# Calliope_mini_rev1_0.net
KiCad netlist of a schematic drawn in EAGLE
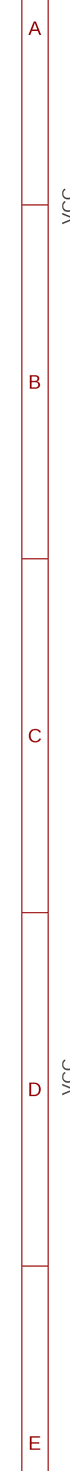
[diagram p0: schematic, sheet 1, part 1 of 2]
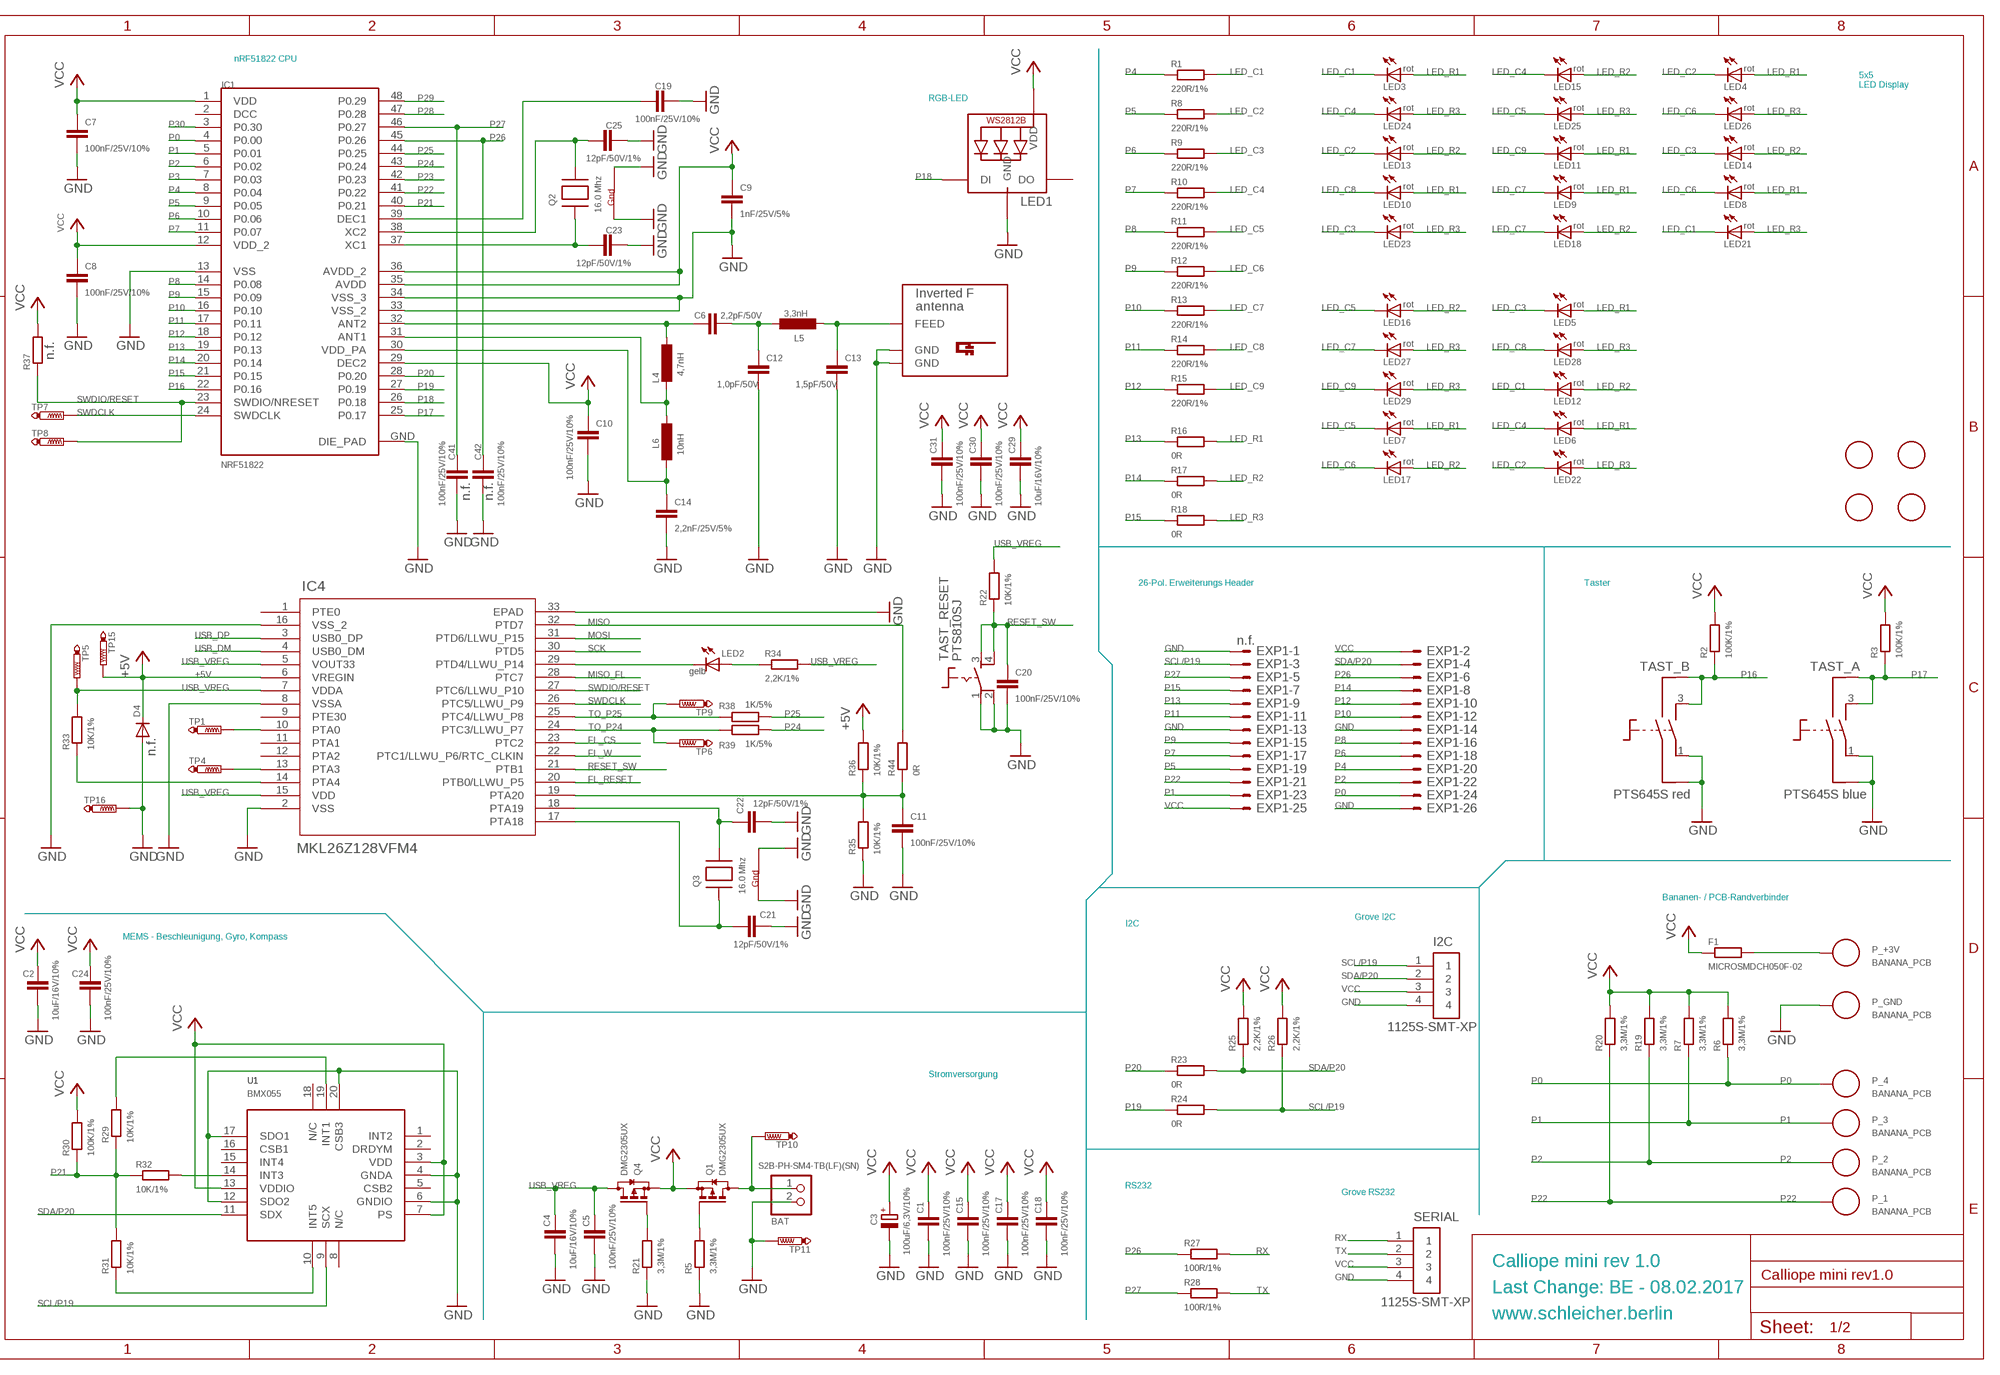
[diagram p1: schematic, sheet 1, part 2 of 2]
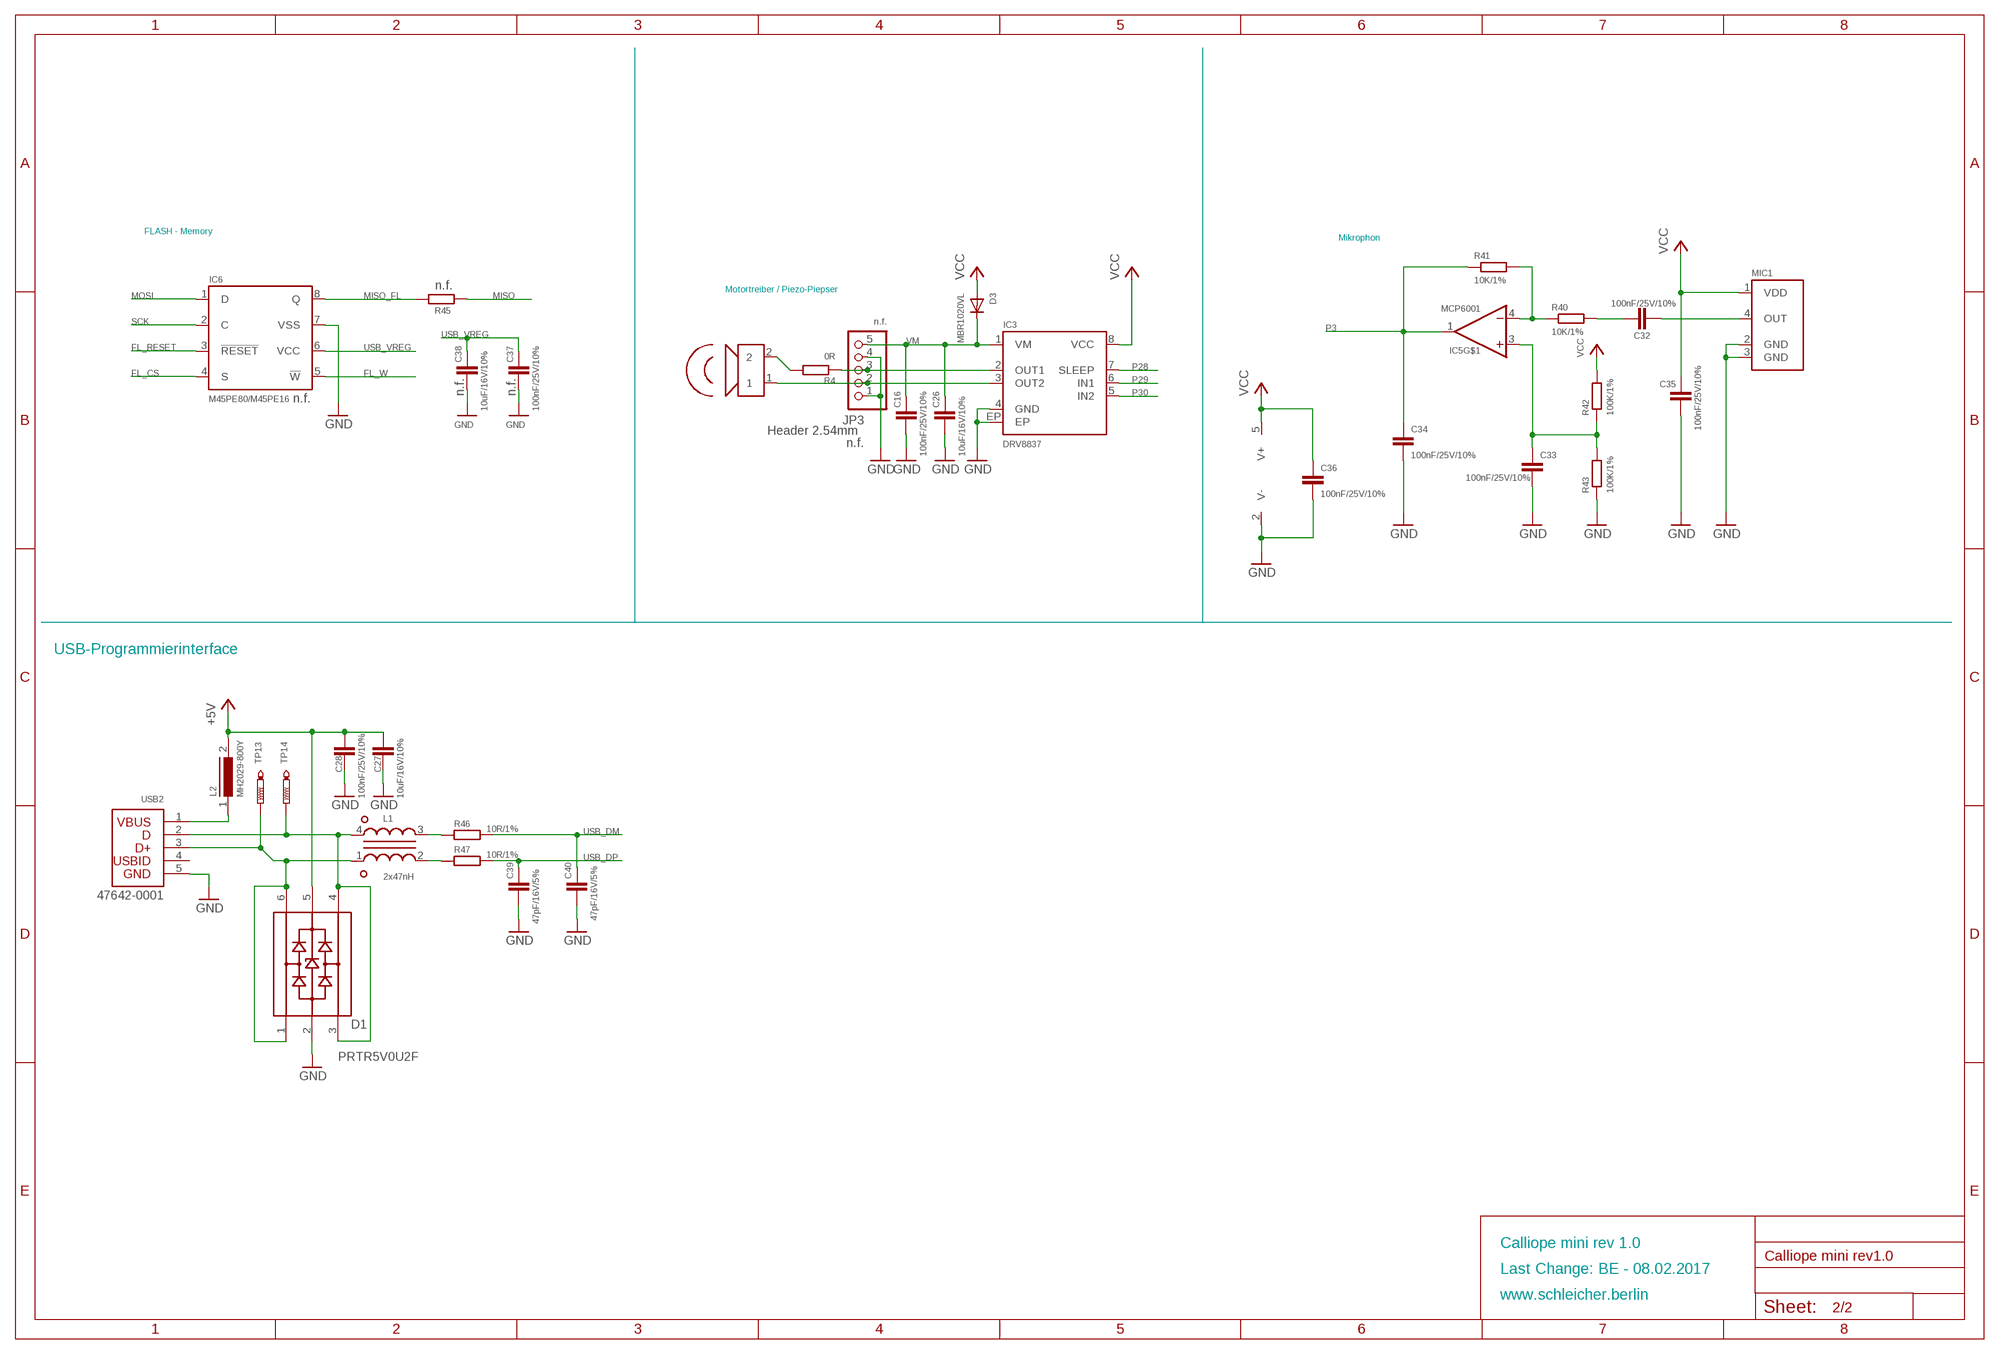
[diagram p2: schematic, sheet 2]

(export (version "E")
  (design (tool "Eeschema 10.0.6"))
  (components
    (comp (ref "C16")
      (value "100nF/25V/10%")
      (footprint "eagle-import:0402")
      (libsource (lib "eagle-import") (part "C-EU0402"))
    )
    (comp (ref "C26")
      (value "10uF/16V/10%")
      (footprint "eagle-import:0603")
      (libsource (lib "eagle-import") (part "C-EU0603"))
    )
    (comp (ref "C27")
      (value "10uF/16V/10%")
      (footprint "eagle-import:0603")
      (libsource (lib "eagle-import") (part "C-EU0603"))
    )
    (comp (ref "C28")
      (value "100nF/25V/10%")
      (footprint "eagle-import:0402")
      (libsource (lib "eagle-import") (part "C-EU0402"))
    )
    (comp (ref "C32")
      (value "100nF/25V/10%")
      (footprint "eagle-import:0402")
      (libsource (lib "eagle-import") (part "C-EU0402"))
    )
    (comp (ref "C33")
      (value "100nF/25V/10%")
      (footprint "eagle-import:0402")
      (libsource (lib "eagle-import") (part "C-EU0402"))
    )
    (comp (ref "C34")
      (value "100nF/25V/10%")
      (footprint "eagle-import:0402")
      (libsource (lib "eagle-import") (part "C-EU0402"))
    )
    (comp (ref "C35")
      (value "100nF/25V/10%")
      (footprint "eagle-import:0402")
      (libsource (lib "eagle-import") (part "C-EU0402"))
    )
    (comp (ref "C36")
      (value "100nF/25V/10%")
      (footprint "eagle-import:0402")
      (libsource (lib "eagle-import") (part "C-EU0402"))
    )
    (comp (ref "C37")
      (value "100nF/25V/10%")
      (footprint "eagle-import:0402")
      (fields (field (name "MOUNTING") "n.f."))
      (libsource (lib "eagle-import") (part "C-EU0402"))
    )
    (comp (ref "C38")
      (value "10uF/16V/10%")
      (footprint "eagle-import:0603")
      (fields (field (name "MOUNTING") "n.f."))
      (libsource (lib "eagle-import") (part "C-EU0603"))
    )
    (comp (ref "C39")
      (value "47pF/16V/5%")
      (footprint "eagle-import:0402")
      (libsource (lib "eagle-import") (part "C-EU0402"))
    )
    (comp (ref "C40")
      (value "47pF/16V/5%")
      (footprint "eagle-import:0402")
      (libsource (lib "eagle-import") (part "C-EU0402"))
    )
    (comp (ref "D1")
      (value "PRTR5V0U2F")
      (footprint "eagle-import:SOT886")
      (libsource (lib "eagle-import") (part "PRTR5V0U2F"))
    )
    (comp (ref "D3")
      (value "MBR1020VL")
      (footprint "eagle-import:SOD-123FL")
      (libsource (lib "eagle-import") (part "DIODE_SOD-123FL"))
    )
    (comp (ref "IC3")
      (value "DRV8837")
      (footprint "eagle-import:WSON8")
      (libsource (lib "eagle-import") (part "DRV8837"))
    )
    (comp (ref "IC5")
      (value "MCP6001")
      (footprint "eagle-import:SOT23-5")
      (libsource (lib "eagle-import") (part "OPAMP_SINGLESOT23-5"))
    )
    (comp (ref "IC6")
      (value "M45PE80/M45PE16")
      (footprint "eagle-import:VQFN8_6X5")
      (fields (field (name "MOUNTING") "n.f."))
      (libsource (lib "eagle-import") (part "M45PE"))
    )
    (comp (ref "JP3")
      (value "Header 2.54mm")
      (footprint "eagle-import:1X05")
      (fields (field (name "MOUNTING") "n.f."))
      (libsource (lib "eagle-import") (part "PINHD-1X5"))
    )
    (comp (ref "L1")
      (value "2x47nH")
      (footprint "eagle-import:USB_2.0_FILTER_0805")
      (libsource (lib "eagle-import") (part "0805USB-901MLC"))
    )
    (comp (ref "L2")
      (value "MH2029-800Y")
      (footprint "eagle-import:FERRIT_0805")
      (fields (field (name "TOLERANCE") "+-25%"))
      (libsource (lib "eagle-import") (part "MH2029-Y800"))
    )
    (comp (ref "MIC1")
      (value "SPU0410HR5H-PB")
      (footprint "eagle-import:SPU0410HR5H-PB")
      (libsource (lib "eagle-import") (part "SPU0410HR5H-PB"))
    )
    (comp (ref "R4")
      (value "0R")
      (footprint "eagle-import:0402")
      (libsource (lib "eagle-import") (part "R-EU_0402"))
    )
    (comp (ref "R40")
      (value "10K/1%")
      (footprint "eagle-import:0402")
      (libsource (lib "eagle-import") (part "R-EU_0402"))
    )
    (comp (ref "R41")
      (value "10K/1%")
      (footprint "eagle-import:0402")
      (libsource (lib "eagle-import") (part "R-EU_0402"))
    )
    (comp (ref "R42")
      (value "100K/1%")
      (footprint "eagle-import:0402")
      (libsource (lib "eagle-import") (part "R-EU_0402"))
    )
    (comp (ref "R43")
      (value "100K/1%")
      (footprint "eagle-import:0402")
      (libsource (lib "eagle-import") (part "R-EU_0402"))
    )
    (comp (ref "R45")
      (value "R-EU_0402")
      (footprint "eagle-import:0402")
      (fields (field (name "MOUNTING") "n.f."))
      (libsource (lib "eagle-import") (part "R-EU_0402"))
    )
    (comp (ref "R46")
      (value "10R/1%")
      (footprint "eagle-import:R0603")
      (libsource (lib "eagle-import") (part "resistor_R-EU_R0603"))
    )
    (comp (ref "R47")
      (value "10R/1%")
      (footprint "eagle-import:R0603")
      (libsource (lib "eagle-import") (part "resistor_R-EU_R0603"))
    )
    (comp (ref "SPK1")
      (value "PKMCS0909E4000-R1")
      (footprint "eagle-import:PKMCS")
      (libsource (lib "eagle-import") (part "PKMCS0909E4000-R1"))
    )
    (comp (ref "TP13")
      (value "PTR1B1,27")
      (footprint "eagle-import:B1,27")
      (libsource (lib "eagle-import") (part "PTR1B1,27"))
    )
    (comp (ref "TP14")
      (value "PTR1B1,27")
      (footprint "eagle-import:B1,27")
      (libsource (lib "eagle-import") (part "PTR1B1,27"))
    )
    (comp (ref "USB2")
      (value "47642-0001")
      (footprint "eagle-import:47642-0001")
      (libsource (lib "eagle-import") (part "47642-0001"))
    )
    (comp (ref "BAT")
      (value "S2B-PH-SM4-TB(LF)(SN)")
      (footprint "eagle-import:JST-PH-2-SMT-RA")
      (libsource (lib "eagle-import") (part "JST_2PIN-SMT-RA"))
    )
    (comp (ref "C1")
      (value "100nF/25V/10%")
      (footprint "eagle-import:0402")
      (libsource (lib "eagle-import") (part "C-EU0402"))
    )
    (comp (ref "C2")
      (value "10uF/16V/10%")
      (footprint "eagle-import:0603")
      (libsource (lib "eagle-import") (part "C-EU0603"))
    )
    (comp (ref "C3")
      (value "100uF/6,3V/10%")
      (footprint "eagle-import:D_7343-31R")
      (libsource (lib "eagle-import") (part "CPOL-EUD/7343-31R"))
    )
    (comp (ref "C4")
      (value "10uF/16V/10%")
      (footprint "eagle-import:0603")
      (libsource (lib "eagle-import") (part "C-EU0603"))
    )
    (comp (ref "C5")
      (value "100nF/25V/10%")
      (footprint "eagle-import:0402")
      (libsource (lib "eagle-import") (part "C-EU0402"))
    )
    (comp (ref "C6")
      (value "2,2pF/50V")
      (footprint "eagle-import:0402")
      (libsource (lib "eagle-import") (part "C-EU0402"))
    )
    (comp (ref "C7")
      (value "100nF/25V/10%")
      (footprint "eagle-import:0402")
      (libsource (lib "eagle-import") (part "C-EU0402"))
    )
    (comp (ref "C8")
      (value "100nF/25V/10%")
      (footprint "eagle-import:0402")
      (libsource (lib "eagle-import") (part "C-EU0402"))
    )
    (comp (ref "C9")
      (value "1nF/25V/5%")
      (footprint "eagle-import:0402")
      (libsource (lib "eagle-import") (part "C-EU0402"))
    )
    (comp (ref "C10")
      (value "100nF/25V/10%")
      (footprint "eagle-import:0402")
      (libsource (lib "eagle-import") (part "C-EU0402"))
    )
    (comp (ref "C11")
      (value "100nF/25V/10%")
      (footprint "eagle-import:0402")
      (libsource (lib "eagle-import") (part "C-EU0402"))
    )
    (comp (ref "C12")
      (value "1,0pF/50V")
      (footprint "eagle-import:0402")
      (libsource (lib "eagle-import") (part "C-EU0402"))
    )
    (comp (ref "C13")
      (value "1,5pF/50V")
      (footprint "eagle-import:0402")
      (libsource (lib "eagle-import") (part "C-EU0402"))
    )
    (comp (ref "C14")
      (value "2,2nF/25V/5%")
      (footprint "eagle-import:0402")
      (libsource (lib "eagle-import") (part "C-EU0402"))
    )
    (comp (ref "C15")
      (value "100nF/25V/10%")
      (footprint "eagle-import:0402")
      (libsource (lib "eagle-import") (part "C-EU0402"))
    )
    (comp (ref "C17")
      (value "100nF/25V/10%")
      (footprint "eagle-import:0402")
      (libsource (lib "eagle-import") (part "C-EU0402"))
    )
    (comp (ref "C18")
      (value "100nF/25V/10%")
      (footprint "eagle-import:0402")
      (libsource (lib "eagle-import") (part "C-EU0402"))
    )
    (comp (ref "C19")
      (value "100nF/25V/10%")
      (footprint "eagle-import:0402")
      (libsource (lib "eagle-import") (part "C-EU0402"))
    )
    (comp (ref "C20")
      (value "100nF/25V/10%")
      (footprint "eagle-import:0402")
      (libsource (lib "eagle-import") (part "C-EU0402"))
    )
    (comp (ref "C21")
      (value "12pF/50V/1%")
      (footprint "eagle-import:0402")
      (libsource (lib "eagle-import") (part "C-EU0402"))
    )
    (comp (ref "C22")
      (value "12pF/50V/1%")
      (footprint "eagle-import:0402")
      (libsource (lib "eagle-import") (part "C-EU0402"))
    )
    (comp (ref "C23")
      (value "12pF/50V/1%")
      (footprint "eagle-import:0402")
      (libsource (lib "eagle-import") (part "C-EU0402"))
    )
    (comp (ref "C24")
      (value "100nF/25V/10%")
      (footprint "eagle-import:0402")
      (libsource (lib "eagle-import") (part "C-EU0402"))
    )
    (comp (ref "C25")
      (value "12pF/50V/1%")
      (footprint "eagle-import:0402")
      (libsource (lib "eagle-import") (part "C-EU0402"))
    )
    (comp (ref "C29")
      (value "10uF/16V/10%")
      (footprint "eagle-import:0603")
      (libsource (lib "eagle-import") (part "C-EU0603"))
    )
    (comp (ref "C30")
      (value "100nF/25V/10%")
      (footprint "eagle-import:0402")
      (libsource (lib "eagle-import") (part "C-EU0402"))
    )
    (comp (ref "C31")
      (value "100nF/25V/10%")
      (footprint "eagle-import:0402")
      (libsource (lib "eagle-import") (part "C-EU0402"))
    )
    (comp (ref "C41")
      (value "100nF/25V/10%")
      (footprint "eagle-import:0402")
      (fields (field (name "MOUNTING") "n.f."))
      (libsource (lib "eagle-import") (part "C-EU0402"))
    )
    (comp (ref "C42")
      (value "100nF/25V/10%")
      (footprint "eagle-import:0402")
      (fields (field (name "MOUNTING") "n.f."))
      (libsource (lib "eagle-import") (part "C-EU0402"))
    )
    (comp (ref "D4")
      (value "DIODE-SOD323-R")
      (footprint "eagle-import:SOD323-R")
      (fields (field (name "MOUNTING") "n.f."))
      (libsource (lib "eagle-import") (part "DIODE-SOD323-R"))
    )
    (comp (ref "EXP1")
      (value "ML26E")
      (footprint "eagle-import:ML26")
      (fields (field (name "MOUNTING") "n.f."))
      (libsource (lib "eagle-import") (part "ML26?E"))
    )
    (comp (ref "F1")
      (value "MICROSMDCH050F-02")
      (footprint "eagle-import:R1210")
      (libsource (lib "eagle-import") (part "R-EU_R1210"))
    )
    (comp (ref "I2C")
      (value "1125S-SMT-XP")
      (footprint "eagle-import:1125S-SMT-XP")
      (libsource (lib "eagle-import") (part "1125-SMT-XPS"))
    )
    (comp (ref "IC1")
      (value "NRF51822")
      (footprint "eagle-import:QFN48")
      (libsource (lib "eagle-import") (part "NRF51822"))
    )
    (comp (ref "IC4")
      (value "MKL26Z128VFM4")
      (footprint "eagle-import:QFN_32_5X5X0P9")
      (libsource (lib "eagle-import") (part "MKL26Z"))
    )
    (comp (ref "L4")
      (value "4,7nH")
      (footprint "eagle-import:0402")
      (libsource (lib "eagle-import") (part "L-EU0402"))
    )
    (comp (ref "L5")
      (value "3,3nH")
      (footprint "eagle-import:0402")
      (libsource (lib "eagle-import") (part "L-EU0402"))
    )
    (comp (ref "L6")
      (value "10nH")
      (footprint "eagle-import:0402")
      (libsource (lib "eagle-import") (part "L-EU0402"))
    )
    (comp (ref "LED1")
      (value "SK6812MINI")
      (footprint "eagle-import:LED3535")
      (libsource (lib "eagle-import") (part "WS2812B3535"))
    )
    (comp (ref "LED2")
      (value "gelb")
      (footprint "eagle-import:CHIPLED_0603")
      (libsource (lib "eagle-import") (part "LEDCHIPLED_0603"))
    )
    (comp (ref "LED3")
      (value "rot")
      (footprint "eagle-import:CHIPLED_0603")
      (libsource (lib "eagle-import") (part "LEDCHIPLED_0603"))
    )
    (comp (ref "LED4")
      (value "rot")
      (footprint "eagle-import:CHIPLED_0603")
      (libsource (lib "eagle-import") (part "LEDCHIPLED_0603"))
    )
    (comp (ref "LED5")
      (value "rot")
      (footprint "eagle-import:CHIPLED_0603")
      (libsource (lib "eagle-import") (part "LEDCHIPLED_0603"))
    )
    (comp (ref "LED6")
      (value "rot")
      (footprint "eagle-import:CHIPLED_0603")
      (libsource (lib "eagle-import") (part "LEDCHIPLED_0603"))
    )
    (comp (ref "LED7")
      (value "rot")
      (footprint "eagle-import:CHIPLED_0603")
      (libsource (lib "eagle-import") (part "LEDCHIPLED_0603"))
    )
    (comp (ref "LED8")
      (value "rot")
      (footprint "eagle-import:CHIPLED_0603")
      (libsource (lib "eagle-import") (part "LEDCHIPLED_0603"))
    )
    (comp (ref "LED9")
      (value "rot")
      (footprint "eagle-import:CHIPLED_0603")
      (libsource (lib "eagle-import") (part "LEDCHIPLED_0603"))
    )
    (comp (ref "LED10")
      (value "rot")
      (footprint "eagle-import:CHIPLED_0603")
      (libsource (lib "eagle-import") (part "LEDCHIPLED_0603"))
    )
    (comp (ref "LED11")
      (value "rot")
      (footprint "eagle-import:CHIPLED_0603")
      (libsource (lib "eagle-import") (part "LEDCHIPLED_0603"))
    )
    (comp (ref "LED12")
      (value "rot")
      (footprint "eagle-import:CHIPLED_0603")
      (libsource (lib "eagle-import") (part "LEDCHIPLED_0603"))
    )
    (comp (ref "LED13")
      (value "rot")
      (footprint "eagle-import:CHIPLED_0603")
      (libsource (lib "eagle-import") (part "LEDCHIPLED_0603"))
    )
    (comp (ref "LED14")
      (value "rot")
      (footprint "eagle-import:CHIPLED_0603")
      (libsource (lib "eagle-import") (part "LEDCHIPLED_0603"))
    )
    (comp (ref "LED15")
      (value "rot")
      (footprint "eagle-import:CHIPLED_0603")
      (libsource (lib "eagle-import") (part "LEDCHIPLED_0603"))
    )
    (comp (ref "LED16")
      (value "rot")
      (footprint "eagle-import:CHIPLED_0603")
      (libsource (lib "eagle-import") (part "LEDCHIPLED_0603"))
    )
    (comp (ref "LED17")
      (value "rot")
      (footprint "eagle-import:CHIPLED_0603")
      (libsource (lib "eagle-import") (part "LEDCHIPLED_0603"))
    )
    (comp (ref "LED18")
      (value "rot")
      (footprint "eagle-import:CHIPLED_0603")
      (libsource (lib "eagle-import") (part "LEDCHIPLED_0603"))
    )
    (comp (ref "LED21")
      (value "rot")
      (footprint "eagle-import:CHIPLED_0603")
      (libsource (lib "eagle-import") (part "LEDCHIPLED_0603"))
    )
    (comp (ref "LED22")
      (value "rot")
      (footprint "eagle-import:CHIPLED_0603")
      (libsource (lib "eagle-import") (part "LEDCHIPLED_0603"))
    )
    (comp (ref "LED23")
      (value "rot")
      (footprint "eagle-import:CHIPLED_0603")
      (libsource (lib "eagle-import") (part "LEDCHIPLED_0603"))
    )
    (comp (ref "LED24")
      (value "rot")
      (footprint "eagle-import:CHIPLED_0603")
      (libsource (lib "eagle-import") (part "LEDCHIPLED_0603"))
    )
    (comp (ref "LED25")
      (value "rot")
      (footprint "eagle-import:CHIPLED_0603")
      (libsource (lib "eagle-import") (part "LEDCHIPLED_0603"))
    )
    (comp (ref "LED26")
      (value "rot")
      (footprint "eagle-import:CHIPLED_0603")
      (libsource (lib "eagle-import") (part "LEDCHIPLED_0603"))
    )
    (comp (ref "LED27")
      (value "rot")
      (footprint "eagle-import:CHIPLED_0603")
      (libsource (lib "eagle-import") (part "LEDCHIPLED_0603"))
    )
    (comp (ref "LED28")
      (value "rot")
      (footprint "eagle-import:CHIPLED_0603")
      (libsource (lib "eagle-import") (part "LEDCHIPLED_0603"))
    )
    (comp (ref "LED29")
      (value "rot")
      (footprint "eagle-import:CHIPLED_0603")
      (libsource (lib "eagle-import") (part "LEDCHIPLED_0603"))
    )
    (comp (ref "P_+3V")
      (value "BANANA_PCB")
      (footprint "eagle-import:BANANA_REC")
      (libsource (lib "eagle-import") (part "BANANA_PCB"))
    )
    (comp (ref "P_1")
      (value "BANANA_PCB")
      (footprint "eagle-import:BANANA_REC")
      (libsource (lib "eagle-import") (part "BANANA_PCB"))
    )
    (comp (ref "P_2")
      (value "BANANA_PCB")
      (footprint "eagle-import:BANANA_REC")
      (libsource (lib "eagle-import") (part "BANANA_PCB"))
    )
    (comp (ref "P_3")
      (value "BANANA_PCB")
      (footprint "eagle-import:BANANA_REC")
      (libsource (lib "eagle-import") (part "BANANA_PCB"))
    )
    (comp (ref "P_4")
      (value "BANANA_PCB")
      (footprint "eagle-import:BANANA_REC")
      (libsource (lib "eagle-import") (part "BANANA_PCB"))
    )
    (comp (ref "P_GND")
      (value "BANANA_PCB")
      (footprint "eagle-import:BANANA_REC")
      (libsource (lib "eagle-import") (part "BANANA_PCB"))
    )
    (comp (ref "Q1")
      (value "DMG2305UX")
      (footprint "eagle-import:SOT23")
      (libsource (lib "eagle-import") (part "BSS84"))
    )
    (comp (ref "Q2")
      (value "16.0 Mhz")
      (footprint "eagle-import:NX3225")
      (libsource (lib "eagle-import") (part "XTAL-4-3225"))
    )
    (comp (ref "Q3")
      (value "16.0 Mhz")
      (footprint "eagle-import:NX3225")
      (libsource (lib "eagle-import") (part "XTAL-4-3225"))
    )
    (comp (ref "Q4")
      (value "DMG2305UX")
      (footprint "eagle-import:SOT23")
      (libsource (lib "eagle-import") (part "BSS84"))
    )
    (comp (ref "R1")
      (value "220R/1%")
      (footprint "eagle-import:0402")
      (libsource (lib "eagle-import") (part "R-EU_0402"))
    )
    (comp (ref "R2")
      (value "100K/1%")
      (footprint "eagle-import:0402")
      (libsource (lib "eagle-import") (part "R-EU_0402"))
    )
    (comp (ref "R3")
      (value "100K/1%")
      (footprint "eagle-import:0402")
      (libsource (lib "eagle-import") (part "R-EU_0402"))
    )
    (comp (ref "R5")
      (value "3,3M/1%")
      (footprint "eagle-import:0402")
      (libsource (lib "eagle-import") (part "R-EU_0402"))
    )
    (comp (ref "R6")
      (value "3,3M/1%")
      (footprint "eagle-import:0402")
      (libsource (lib "eagle-import") (part "R-EU_0402"))
    )
    (comp (ref "R7")
      (value "3,3M/1%")
      (footprint "eagle-import:0402")
      (libsource (lib "eagle-import") (part "R-EU_0402"))
    )
    (comp (ref "R8")
      (value "220R/1%")
      (footprint "eagle-import:0402")
      (libsource (lib "eagle-import") (part "R-EU_0402"))
    )
    (comp (ref "R9")
      (value "220R/1%")
      (footprint "eagle-import:0402")
      (libsource (lib "eagle-import") (part "R-EU_0402"))
    )
    (comp (ref "R10")
      (value "220R/1%")
      (footprint "eagle-import:0402")
      (libsource (lib "eagle-import") (part "R-EU_0402"))
    )
    (comp (ref "R11")
      (value "220R/1%")
      (footprint "eagle-import:0402")
      (libsource (lib "eagle-import") (part "R-EU_0402"))
    )
    (comp (ref "R12")
      (value "220R/1%")
      (footprint "eagle-import:0402")
      (libsource (lib "eagle-import") (part "R-EU_0402"))
    )
    (comp (ref "R13")
      (value "220R/1%")
      (footprint "eagle-import:0402")
      (libsource (lib "eagle-import") (part "R-EU_0402"))
    )
    (comp (ref "R14")
      (value "220R/1%")
      (footprint "eagle-import:0402")
      (libsource (lib "eagle-import") (part "R-EU_0402"))
    )
    (comp (ref "R15")
      (value "220R/1%")
      (footprint "eagle-import:0402")
      (libsource (lib "eagle-import") (part "R-EU_0402"))
    )
    (comp (ref "R16")
      (value "0R")
      (footprint "eagle-import:0402")
      (libsource (lib "eagle-import") (part "R-EU_0402"))
    )
    (comp (ref "R17")
      (value "0R")
      (footprint "eagle-import:0402")
      (libsource (lib "eagle-import") (part "R-EU_0402"))
    )
    (comp (ref "R18")
      (value "0R")
      (footprint "eagle-import:0402")
      (libsource (lib "eagle-import") (part "R-EU_0402"))
    )
    (comp (ref "R19")
      (value "3,3M/1%")
      (footprint "eagle-import:0402")
      (libsource (lib "eagle-import") (part "R-EU_0402"))
    )
    (comp (ref "R20")
      (value "3,3M/1%")
      (footprint "eagle-import:0402")
      (libsource (lib "eagle-import") (part "R-EU_0402"))
    )
    (comp (ref "R21")
      (value "3,3M/1%")
      (footprint "eagle-import:0402")
      (libsource (lib "eagle-import") (part "R-EU_0402"))
    )
    (comp (ref "R22")
      (value "10K/1%")
      (footprint "eagle-import:0402")
      (libsource (lib "eagle-import") (part "R-EU_0402"))
    )
    (comp (ref "R23")
      (value "0R")
      (footprint "eagle-import:0402")
      (libsource (lib "eagle-import") (part "R-EU_0402"))
    )
    (comp (ref "R24")
      (value "0R")
      (footprint "eagle-import:0402")
      (libsource (lib "eagle-import") (part "R-EU_0402"))
    )
    (comp (ref "R25")
      (value "2,2K/1%")
      (footprint "eagle-import:0402")
      (libsource (lib "eagle-import") (part "R-EU_0402"))
    )
    (comp (ref "R26")
      (value "2,2K/1%")
      (footprint "eagle-import:0402")
      (libsource (lib "eagle-import") (part "R-EU_0402"))
    )
    (comp (ref "R27")
      (value "100R/1%")
      (footprint "eagle-import:0402")
      (libsource (lib "eagle-import") (part "R-EU_0402"))
    )
    (comp (ref "R28")
      (value "100R/1%")
      (footprint "eagle-import:0402")
      (libsource (lib "eagle-import") (part "R-EU_0402"))
    )
    (comp (ref "R29")
      (value "10K/1%")
      (footprint "eagle-import:0402")
      (libsource (lib "eagle-import") (part "R-EU_0402"))
    )
    (comp (ref "R30")
      (value "100K/1%")
      (footprint "eagle-import:0402")
      (libsource (lib "eagle-import") (part "R-EU_0402"))
    )
    (comp (ref "R31")
      (value "10K/1%")
      (footprint "eagle-import:0402")
      (libsource (lib "eagle-import") (part "R-EU_0402"))
    )
    (comp (ref "R32")
      (value "10K/1%")
      (footprint "eagle-import:0402")
      (libsource (lib "eagle-import") (part "R-EU_0402"))
    )
    (comp (ref "R33")
      (value "10K/1%")
      (footprint "eagle-import:0402")
      (libsource (lib "eagle-import") (part "R-EU_0402"))
    )
    (comp (ref "R34")
      (value "2,2K/1%")
      (footprint "eagle-import:0402")
      (libsource (lib "eagle-import") (part "R-EU_0402"))
    )
    (comp (ref "R35")
      (value "10K/1%")
      (footprint "eagle-import:0402")
      (libsource (lib "eagle-import") (part "R-EU_0402"))
    )
    (comp (ref "R36")
      (value "10K/1%")
      (footprint "eagle-import:0402")
      (libsource (lib "eagle-import") (part "R-EU_0402"))
    )
    (comp (ref "R37")
      (value "R-EU_0402")
      (footprint "eagle-import:0402")
      (fields (field (name "MOUNTING") "n.f."))
      (libsource (lib "eagle-import") (part "R-EU_0402"))
    )
    (comp (ref "R38")
      (value "1K/5%")
      (footprint "eagle-import:0402")
      (libsource (lib "eagle-import") (part "R-EU_0402"))
    )
    (comp (ref "R39")
      (value "1K/5%")
      (footprint "eagle-import:0402")
      (libsource (lib "eagle-import") (part "R-EU_0402"))
    )
    (comp (ref "R44")
      (value "0R")
      (footprint "eagle-import:0402")
      (libsource (lib "eagle-import") (part "R-EU_0402"))
    )
    (comp (ref "SERIAL")
      (value "1125S-SMT-XP")
      (footprint "eagle-import:1125S-SMT-XP")
      (libsource (lib "eagle-import") (part "1125-SMT-XPS"))
    )
    (comp (ref "TAST_A")
      (value "PTS645S blue")
      (footprint "eagle-import:PTS645S")
      (libsource (lib "eagle-import") (part "PTS645S"))
    )
    (comp (ref "TAST_B")
      (value "PTS645S red")
      (footprint "eagle-import:PTS645S")
      (libsource (lib "eagle-import") (part "PTS645S"))
    )
    (comp (ref "TAST_RESET")
      (value "PTS810SJ")
      (footprint "eagle-import:PTS810")
      (libsource (lib "eagle-import") (part "PTS810SJ"))
    )
    (comp (ref "TP1")
      (value "PTR1B1,27")
      (footprint "eagle-import:B1,27")
      (libsource (lib "eagle-import") (part "PTR1B1,27"))
    )
    (comp (ref "TP4")
      (value "PTR1B1,27")
      (footprint "eagle-import:B1,27")
      (libsource (lib "eagle-import") (part "PTR1B1,27"))
    )
    (comp (ref "TP5")
      (value "PTR1B1,27")
      (footprint "eagle-import:B1,27")
      (libsource (lib "eagle-import") (part "PTR1B1,27"))
    )
    (comp (ref "TP6")
      (value "PTR1B1,27")
      (footprint "eagle-import:B1,27")
      (libsource (lib "eagle-import") (part "PTR1B1,27"))
    )
    (comp (ref "TP7")
      (value "PTR1B1,27")
      (footprint "eagle-import:B1,27")
      (libsource (lib "eagle-import") (part "PTR1B1,27"))
    )
    (comp (ref "TP8")
      (value "PTR1B1,27")
      (footprint "eagle-import:B1,27")
      (libsource (lib "eagle-import") (part "PTR1B1,27"))
    )
    (comp (ref "TP9")
      (value "PTR1B1,27")
      (footprint "eagle-import:B1,27")
      (libsource (lib "eagle-import") (part "PTR1B1,27"))
    )
    (comp (ref "TP10")
      (value "PTR1B1,27")
      (footprint "eagle-import:B1,27")
      (libsource (lib "eagle-import") (part "PTR1B1,27"))
    )
    (comp (ref "TP11")
      (value "PTR1B1,27")
      (footprint "eagle-import:B1,27")
      (libsource (lib "eagle-import") (part "PTR1B1,27"))
    )
    (comp (ref "TP15")
      (value "PTR1B1,27")
      (footprint "eagle-import:B1,27")
      (libsource (lib "eagle-import") (part "PTR1B1,27"))
    )
    (comp (ref "TP16")
      (value "PTR1B1,27")
      (footprint "eagle-import:B1,27")
      (libsource (lib "eagle-import") (part "PTR1B1,27"))
    )
    (comp (ref "U$2")
      (value "INVERTED_F_ANTENNA")
      (footprint "eagle-import:DN0007+0_MIRROR")
      (libsource (lib "eagle-import") (part "INVERTED_F_ANTENNA"))
    )
    (comp (ref "U$5")
      (value "FIDUCIAL")
      (footprint "eagle-import:FIDUCIAL_1MM")
      (libsource (lib "eagle-import") (part "FIDUCIAL"))
    )
    (comp (ref "U$6")
      (value "FIDUCIAL")
      (footprint "eagle-import:FIDUCIAL_1MM")
      (libsource (lib "eagle-import") (part "FIDUCIAL"))
    )
    (comp (ref "U$7")
      (value "FIDUCIAL")
      (footprint "eagle-import:FIDUCIAL_1MM")
      (libsource (lib "eagle-import") (part "FIDUCIAL"))
    )
    (comp (ref "U$8")
      (value "FIDUCIAL")
      (footprint "eagle-import:FIDUCIAL_1MM")
      (libsource (lib "eagle-import") (part "FIDUCIAL"))
    )
    (comp (ref "U1")
      (value "BMX055")
      (footprint "eagle-import:BMX055")
      (libsource (lib "eagle-import") (part "BMX055"))
    )
  )
  (nets
    (net (code "1") (name "+5V") (class "Default")
      (node (ref "C27") (pin "1") (pinfunction "1_1") (pintype "passive"))
      (node (ref "C28") (pin "1") (pinfunction "1_1") (pintype "passive"))
      (node (ref "D1") (pin "5") (pinfunction "5_5") (pintype "bidirectional"))
      (node (ref "D4") (pin "C") (pinfunction "C_C") (pintype "passive"))
      (node (ref "IC4") (pin "6") (pinfunction "VREGIN_6") (pintype "input"))
      (node (ref "L2") (pin "2") (pinfunction "2_2") (pintype "passive"))
      (node (ref "R36") (pin "2") (pinfunction "2_2") (pintype "passive"))
      (node (ref "TP15") (pin "TP") (pinfunction "TP_TP") (pintype "input"))
    )
    (net (code "2") (name "FL_CS") (class "Default")
      (node (ref "IC4") (pin "23") (pinfunction "PTC2_23") (pintype "bidirectional"))
      (node (ref "IC6") (pin "4") (pinfunction "S_4") (pintype "bidirectional"))
    )
    (net (code "3") (name "FL_RESET") (class "Default")
      (node (ref "IC4") (pin "20") (pinfunction "PTB0/LLWU_P5_20") (pintype "bidirectional"))
      (node (ref "IC6") (pin "3") (pinfunction "~{RESET}_3") (pintype "bidirectional"))
    )
    (net (code "4") (name "FL_W") (class "Default")
      (node (ref "IC4") (pin "22") (pinfunction "PTC1/LLWU_P6/RTC_CLKIN_22") (pintype "bidirectional"))
      (node (ref "IC6") (pin "5") (pinfunction "~{W}_5") (pintype "bidirectional"))
    )
    (net (code "5") (name "GND") (class "Default")
      (node (ref "BAT") (pin "2") (pinfunction "1_2") (pintype "passive"))
      (node (ref "C1") (pin "2") (pinfunction "2_2") (pintype "passive"))
      (node (ref "C10") (pin "2") (pinfunction "2_2") (pintype "passive"))
      (node (ref "C11") (pin "2") (pinfunction "2_2") (pintype "passive"))
      (node (ref "C12") (pin "2") (pinfunction "2_2") (pintype "passive"))
      (node (ref "C13") (pin "2") (pinfunction "2_2") (pintype "passive"))
      (node (ref "C14") (pin "2") (pinfunction "2_2") (pintype "passive"))
      (node (ref "C15") (pin "2") (pinfunction "2_2") (pintype "passive"))
      (node (ref "C16") (pin "2") (pinfunction "2_2") (pintype "passive"))
      (node (ref "C17") (pin "2") (pinfunction "2_2") (pintype "passive"))
      (node (ref "C18") (pin "2") (pinfunction "2_2") (pintype "passive"))
      (node (ref "C19") (pin "2") (pinfunction "2_2") (pintype "passive"))
      (node (ref "C2") (pin "2") (pinfunction "2_2") (pintype "passive"))
      (node (ref "C20") (pin "2") (pinfunction "2_2") (pintype "passive"))
      (node (ref "C21") (pin "2") (pinfunction "2_2") (pintype "passive"))
      (node (ref "C22") (pin "2") (pinfunction "2_2") (pintype "passive"))
      (node (ref "C23") (pin "2") (pinfunction "2_2") (pintype "passive"))
      (node (ref "C24") (pin "2") (pinfunction "2_2") (pintype "passive"))
      (node (ref "C25") (pin "2") (pinfunction "2_2") (pintype "passive"))
      (node (ref "C26") (pin "2") (pinfunction "2_2") (pintype "passive"))
      (node (ref "C27") (pin "2") (pinfunction "2_2") (pintype "passive"))
      (node (ref "C28") (pin "2") (pinfunction "2_2") (pintype "passive"))
      (node (ref "C29") (pin "2") (pinfunction "2_2") (pintype "passive"))
      (node (ref "C3") (pin "-") (pinfunction "-_-") (pintype "passive"))
      (node (ref "C30") (pin "2") (pinfunction "2_2") (pintype "passive"))
      (node (ref "C31") (pin "2") (pinfunction "2_2") (pintype "passive"))
      (node (ref "C33") (pin "2") (pinfunction "2_2") (pintype "passive"))
      (node (ref "C34") (pin "2") (pinfunction "2_2") (pintype "passive"))
      (node (ref "C35") (pin "2") (pinfunction "2_2") (pintype "passive"))
      (node (ref "C36") (pin "2") (pinfunction "2_2") (pintype "passive"))
      (node (ref "C37") (pin "2") (pinfunction "2_2") (pintype "passive"))
      (node (ref "C38") (pin "2") (pinfunction "2_2") (pintype "passive"))
      (node (ref "C39") (pin "2") (pinfunction "2_2") (pintype "passive"))
      (node (ref "C4") (pin "2") (pinfunction "2_2") (pintype "passive"))
      (node (ref "C40") (pin "2") (pinfunction "2_2") (pintype "passive"))
      (node (ref "C41") (pin "2") (pinfunction "2_2") (pintype "passive"))
      (node (ref "C42") (pin "2") (pinfunction "2_2") (pintype "passive"))
      (node (ref "C5") (pin "2") (pinfunction "2_2") (pintype "passive"))
      (node (ref "C7") (pin "2") (pinfunction "2_2") (pintype "passive"))
      (node (ref "C8") (pin "2") (pinfunction "2_2") (pintype "passive"))
      (node (ref "C9") (pin "2") (pinfunction "2_2") (pintype "passive"))
      (node (ref "D1") (pin "2") (pinfunction "2_2") (pintype "bidirectional"))
      (node (ref "D4") (pin "A") (pinfunction "A_A") (pintype "passive"))
      (node (ref "EXP1") (pin "1") (pinfunction "S_1") (pintype "passive"))
      (node (ref "EXP1") (pin "13") (pinfunction "S_13") (pintype "passive"))
      (node (ref "EXP1") (pin "14") (pinfunction "S_14") (pintype "passive"))
      (node (ref "EXP1") (pin "26") (pinfunction "S_26") (pintype "passive"))
      (node (ref "I2C") (pin "4") (pinfunction "4_4") (pintype "bidirectional"))
      (node (ref "IC1") (pin "13") (pinfunction "VSS_13") (pintype "bidirectional"))
      (node (ref "IC1") (pin "33") (pinfunction "VSS_2_33") (pintype "bidirectional"))
      (node (ref "IC1") (pin "34") (pinfunction "VSS_3_34") (pintype "bidirectional"))
      (node (ref "IC1") (pin "GND") (pinfunction "DIE_PAD_GND") (pintype "bidirectional"))
      (node (ref "IC3") (pin "4") (pinfunction "GND_4") (pintype "bidirectional"))
      (node (ref "IC3") (pin "EP") (pinfunction "EP_EP") (pintype "bidirectional"))
      (node (ref "IC4") (pin "16") (pinfunction "VSS_2_16") (pintype "power_in"))
      (node (ref "IC4") (pin "2") (pinfunction "VSS_2") (pintype "power_in"))
      (node (ref "IC4") (pin "33") (pinfunction "EPAD_33") (pintype "passive"))
      (node (ref "IC4") (pin "8") (pinfunction "VSSA_8") (pintype "power_in"))
      (node (ref "IC5") (pin "2") (pinfunction "V-_2") (pintype "power_in"))
      (node (ref "IC6") (pin "7") (pinfunction "VSS_7") (pintype "bidirectional"))
      (node (ref "JP3") (pin "1") (pinfunction "1_1") (pintype "passive"))
      (node (ref "JP3") (pin "4") (pinfunction "4_4") (pintype "passive"))
      (node (ref "LED1") (pin "4") (pinfunction "GND_4") (pintype "power_in"))
      (node (ref "MIC1") (pin "2") (pinfunction "GND_2") (pintype "bidirectional"))
      (node (ref "MIC1") (pin "3") (pinfunction "GND_3") (pintype "bidirectional"))
      (node (ref "P_GND") (pin "1") (pinfunction "1_1") (pintype "bidirectional"))
      (node (ref "Q2") (pin "2") (pinfunction "G2_2") (pintype "power_in"))
      (node (ref "Q2") (pin "4") (pinfunction "G1_4") (pintype "power_in"))
      (node (ref "Q3") (pin "2") (pinfunction "G2_2") (pintype "power_in"))
      (node (ref "Q3") (pin "4") (pinfunction "G1_4") (pintype "power_in"))
      (node (ref "R21") (pin "1") (pinfunction "1_1") (pintype "passive"))
      (node (ref "R35") (pin "1") (pinfunction "1_1") (pintype "passive"))
      (node (ref "R43") (pin "1") (pinfunction "1_1") (pintype "passive"))
      (node (ref "R5") (pin "1") (pinfunction "1_1") (pintype "passive"))
      (node (ref "SERIAL") (pin "4") (pinfunction "4_4") (pintype "bidirectional"))
      (node (ref "TAST_A") (pin "1") (pinfunction "P1_1") (pintype "passive"))
      (node (ref "TAST_A") (pin "2") (pinfunction "P2_2") (pintype "passive"))
      (node (ref "TAST_B") (pin "1") (pinfunction "P1_1") (pintype "passive"))
      (node (ref "TAST_B") (pin "2") (pinfunction "P2_2") (pintype "passive"))
      (node (ref "TAST_RESET") (pin "1") (pinfunction "P_1") (pintype "passive"))
      (node (ref "TAST_RESET") (pin "2") (pinfunction "P1_2") (pintype "passive"))
      (node (ref "TP11") (pin "TP") (pinfunction "TP_TP") (pintype "input"))
      (node (ref "TP16") (pin "TP") (pinfunction "TP_TP") (pintype "input"))
      (node (ref "U$2") (pin "GND") (pinfunction "GND_GND") (pintype "bidirectional"))
      (node (ref "U$2") (pin "GND@1") (pinfunction "GND_GND@1") (pintype "bidirectional"))
      (node (ref "U1") (pin "12") (pinfunction "SDO2_12") (pintype "bidirectional"))
      (node (ref "U1") (pin "17") (pinfunction "SDO1_17") (pintype "bidirectional"))
      (node (ref "U1") (pin "20") (pinfunction "CSB3_20") (pintype "bidirectional"))
      (node (ref "U1") (pin "4") (pinfunction "GNDA_4") (pintype "bidirectional"))
      (node (ref "U1") (pin "6") (pinfunction "GNDIO_6") (pintype "bidirectional"))
      (node (ref "USB2") (pin "5") (pinfunction "5_5") (pintype "bidirectional"))
    )
    (net (code "6") (name "LED_C1") (class "Default")
      (node (ref "LED12") (pin "A") (pinfunction "A_A") (pintype "passive"))
      (node (ref "LED21") (pin "A") (pinfunction "A_A") (pintype "passive"))
      (node (ref "LED3") (pin "A") (pinfunction "A_A") (pintype "passive"))
      (node (ref "R1") (pin "2") (pinfunction "2_2") (pintype "passive"))
    )
    (net (code "7") (name "LED_C2") (class "Default")
      (node (ref "LED13") (pin "A") (pinfunction "A_A") (pintype "passive"))
      (node (ref "LED22") (pin "A") (pinfunction "A_A") (pintype "passive"))
      (node (ref "LED4") (pin "A") (pinfunction "A_A") (pintype "passive"))
      (node (ref "R8") (pin "2") (pinfunction "2_2") (pintype "passive"))
    )
    (net (code "8") (name "LED_C3") (class "Default")
      (node (ref "LED14") (pin "A") (pinfunction "A_A") (pintype "passive"))
      (node (ref "LED23") (pin "A") (pinfunction "A_A") (pintype "passive"))
      (node (ref "LED5") (pin "A") (pinfunction "A_A") (pintype "passive"))
      (node (ref "R9") (pin "2") (pinfunction "2_2") (pintype "passive"))
    )
    (net (code "9") (name "LED_C4") (class "Default")
      (node (ref "LED15") (pin "A") (pinfunction "A_A") (pintype "passive"))
      (node (ref "LED24") (pin "A") (pinfunction "A_A") (pintype "passive"))
      (node (ref "LED6") (pin "A") (pinfunction "A_A") (pintype "passive"))
      (node (ref "R10") (pin "2") (pinfunction "2_2") (pintype "passive"))
    )
    (net (code "10") (name "LED_C5") (class "Default")
      (node (ref "LED16") (pin "A") (pinfunction "A_A") (pintype "passive"))
      (node (ref "LED25") (pin "A") (pinfunction "A_A") (pintype "passive"))
      (node (ref "LED7") (pin "A") (pinfunction "A_A") (pintype "passive"))
      (node (ref "R11") (pin "2") (pinfunction "2_2") (pintype "passive"))
    )
    (net (code "11") (name "LED_C6") (class "Default")
      (node (ref "LED17") (pin "A") (pinfunction "A_A") (pintype "passive"))
      (node (ref "LED26") (pin "A") (pinfunction "A_A") (pintype "passive"))
      (node (ref "LED8") (pin "A") (pinfunction "A_A") (pintype "passive"))
      (node (ref "R12") (pin "2") (pinfunction "2_2") (pintype "passive"))
    )
    (net (code "12") (name "LED_C7") (class "Default")
      (node (ref "LED18") (pin "A") (pinfunction "A_A") (pintype "passive"))
      (node (ref "LED27") (pin "A") (pinfunction "A_A") (pintype "passive"))
      (node (ref "LED9") (pin "A") (pinfunction "A_A") (pintype "passive"))
      (node (ref "R13") (pin "2") (pinfunction "2_2") (pintype "passive"))
    )
    (net (code "13") (name "LED_C8") (class "Default")
      (node (ref "LED10") (pin "A") (pinfunction "A_A") (pintype "passive"))
      (node (ref "LED28") (pin "A") (pinfunction "A_A") (pintype "passive"))
      (node (ref "R14") (pin "2") (pinfunction "2_2") (pintype "passive"))
    )
    (net (code "14") (name "LED_C9") (class "Default")
      (node (ref "LED11") (pin "A") (pinfunction "A_A") (pintype "passive"))
      (node (ref "LED29") (pin "A") (pinfunction "A_A") (pintype "passive"))
      (node (ref "R15") (pin "2") (pinfunction "2_2") (pintype "passive"))
    )
    (net (code "15") (name "LED_R1") (class "Default")
      (node (ref "LED10") (pin "C") (pinfunction "C_C") (pintype "passive"))
      (node (ref "LED11") (pin "C") (pinfunction "C_C") (pintype "passive"))
      (node (ref "LED3") (pin "C") (pinfunction "C_C") (pintype "passive"))
      (node (ref "LED4") (pin "C") (pinfunction "C_C") (pintype "passive"))
      (node (ref "LED5") (pin "C") (pinfunction "C_C") (pintype "passive"))
      (node (ref "LED6") (pin "C") (pinfunction "C_C") (pintype "passive"))
      (node (ref "LED7") (pin "C") (pinfunction "C_C") (pintype "passive"))
      (node (ref "LED8") (pin "C") (pinfunction "C_C") (pintype "passive"))
      (node (ref "LED9") (pin "C") (pinfunction "C_C") (pintype "passive"))
      (node (ref "R16") (pin "2") (pinfunction "2_2") (pintype "passive"))
    )
    (net (code "16") (name "LED_R2") (class "Default")
      (node (ref "LED12") (pin "C") (pinfunction "C_C") (pintype "passive"))
      (node (ref "LED13") (pin "C") (pinfunction "C_C") (pintype "passive"))
      (node (ref "LED14") (pin "C") (pinfunction "C_C") (pintype "passive"))
      (node (ref "LED15") (pin "C") (pinfunction "C_C") (pintype "passive"))
      (node (ref "LED16") (pin "C") (pinfunction "C_C") (pintype "passive"))
      (node (ref "LED17") (pin "C") (pinfunction "C_C") (pintype "passive"))
      (node (ref "LED18") (pin "C") (pinfunction "C_C") (pintype "passive"))
      (node (ref "R17") (pin "2") (pinfunction "2_2") (pintype "passive"))
    )
    (net (code "17") (name "LED_R3") (class "Default")
      (node (ref "LED21") (pin "C") (pinfunction "C_C") (pintype "passive"))
      (node (ref "LED22") (pin "C") (pinfunction "C_C") (pintype "passive"))
      (node (ref "LED23") (pin "C") (pinfunction "C_C") (pintype "passive"))
      (node (ref "LED24") (pin "C") (pinfunction "C_C") (pintype "passive"))
      (node (ref "LED25") (pin "C") (pinfunction "C_C") (pintype "passive"))
      (node (ref "LED26") (pin "C") (pinfunction "C_C") (pintype "passive"))
      (node (ref "LED27") (pin "C") (pinfunction "C_C") (pintype "passive"))
      (node (ref "LED28") (pin "C") (pinfunction "C_C") (pintype "passive"))
      (node (ref "LED29") (pin "C") (pinfunction "C_C") (pintype "passive"))
      (node (ref "R18") (pin "2") (pinfunction "2_2") (pintype "passive"))
    )
    (net (code "18") (name "MISO") (class "Default")
      (node (ref "IC4") (pin "32") (pinfunction "PTD7_32") (pintype "bidirectional"))
      (node (ref "R44") (pin "2") (pinfunction "2_2") (pintype "passive"))
      (node (ref "R45") (pin "1") (pinfunction "1_1") (pintype "passive"))
    )
    (net (code "19") (name "MISO_FL") (class "Default")
      (node (ref "IC4") (pin "28") (pinfunction "PTC7_28") (pintype "bidirectional"))
      (node (ref "IC6") (pin "8") (pinfunction "Q_8") (pintype "bidirectional"))
      (node (ref "R45") (pin "2") (pinfunction "2_2") (pintype "passive"))
    )
    (net (code "20") (name "MOSI") (class "Default")
      (node (ref "IC4") (pin "31") (pinfunction "PTD6/LLWU_P15_31") (pintype "bidirectional"))
      (node (ref "IC6") (pin "1") (pinfunction "D_1") (pintype "bidirectional"))
    )
    (net (code "21") (name "Net-(BAT-2)") (class "Default")
      (node (ref "BAT") (pin "1") (pinfunction "2_1") (pintype "passive"))
      (node (ref "Q1") (pin "3") (pinfunction "D_3") (pintype "passive"))
      (node (ref "TP10") (pin "TP") (pinfunction "TP_TP") (pintype "input"))
    )
    (net (code "22") (name "Net-(C12-Pad1)") (class "Default")
      (node (ref "C12") (pin "1") (pinfunction "1_1") (pintype "passive"))
      (node (ref "C6") (pin "2") (pinfunction "2_2") (pintype "passive"))
      (node (ref "L5") (pin "1") (pinfunction "1_1") (pintype "passive"))
    )
    (net (code "23") (name "Net-(C13-Pad1)") (class "Default")
      (node (ref "C13") (pin "1") (pinfunction "1_1") (pintype "passive"))
      (node (ref "L5") (pin "2") (pinfunction "2_2") (pintype "passive"))
      (node (ref "U$2") (pin "FEED") (pinfunction "FEED_FEED") (pintype "bidirectional"))
    )
    (net (code "24") (name "Net-(C32-Pad1)") (class "Default")
      (node (ref "C32") (pin "1") (pinfunction "1_1") (pintype "passive"))
      (node (ref "R40") (pin "2") (pinfunction "2_2") (pintype "passive"))
    )
    (net (code "25") (name "Net-(D1-Pad1)") (class "Default")
      (node (ref "D1") (pin "1") (pinfunction "1_1") (pintype "bidirectional"))
      (node (ref "D1") (pin "6") (pinfunction "6_6") (pintype "bidirectional"))
      (node (ref "L1") (pin "1") (pinfunction "1_1") (pintype "passive"))
      (node (ref "TP13") (pin "TP") (pinfunction "TP_TP") (pintype "input"))
      (node (ref "USB2") (pin "3") (pinfunction "3_3") (pintype "bidirectional"))
    )
    (net (code "26") (name "Net-(F1-Pad2)") (class "Default")
      (node (ref "F1") (pin "2") (pinfunction "2_2") (pintype "passive"))
      (node (ref "P_+3V") (pin "1") (pinfunction "1_1") (pintype "bidirectional"))
    )
    (net (code "27") (name "Net-(IC1-ANT1)") (class "Default")
      (node (ref "IC1") (pin "31") (pinfunction "ANT1_31") (pintype "bidirectional"))
      (node (ref "L4") (pin "2") (pinfunction "2_2") (pintype "passive"))
      (node (ref "L6") (pin "2") (pinfunction "2_2") (pintype "passive"))
    )
    (net (code "28") (name "Net-(IC1-ANT2)") (class "Default")
      (node (ref "C6") (pin "1") (pinfunction "1_1") (pintype "passive"))
      (node (ref "IC1") (pin "32") (pinfunction "ANT2_32") (pintype "bidirectional"))
      (node (ref "L4") (pin "1") (pinfunction "1_1") (pintype "passive"))
    )
    (net (code "29") (name "Net-(IC1-DEC1)") (class "Default")
      (node (ref "C19") (pin "1") (pinfunction "1_1") (pintype "passive"))
      (node (ref "IC1") (pin "39") (pinfunction "DEC1_39") (pintype "bidirectional"))
    )
    (net (code "30") (name "Net-(IC1-VDD_PA)") (class "Default")
      (node (ref "C14") (pin "1") (pinfunction "1_1") (pintype "passive"))
      (node (ref "IC1") (pin "30") (pinfunction "VDD_PA_30") (pintype "bidirectional"))
      (node (ref "L6") (pin "1") (pinfunction "1_1") (pintype "passive"))
    )
    (net (code "31") (name "Net-(IC1-XC1)") (class "Default")
      (node (ref "C23") (pin "1") (pinfunction "1_1") (pintype "passive"))
      (node (ref "IC1") (pin "37") (pinfunction "XC1_37") (pintype "bidirectional"))
      (node (ref "Q2") (pin "1") (pinfunction "X1_1") (pintype "bidirectional"))
    )
    (net (code "32") (name "Net-(IC1-XC2)") (class "Default")
      (node (ref "C25") (pin "1") (pinfunction "1_1") (pintype "passive"))
      (node (ref "IC1") (pin "38") (pinfunction "XC2_38") (pintype "bidirectional"))
      (node (ref "Q2") (pin "3") (pinfunction "X2_3") (pintype "bidirectional"))
    )
    (net (code "33") (name "Net-(IC3-OUT1)") (class "Default")
      (node (ref "IC3") (pin "2") (pinfunction "OUT1_2") (pintype "bidirectional"))
      (node (ref "JP3") (pin "3") (pinfunction "3_3") (pintype "passive"))
      (node (ref "R4") (pin "1") (pinfunction "1_1") (pintype "passive"))
    )
    (net (code "34") (name "Net-(IC3-OUT2)") (class "Default")
      (node (ref "IC3") (pin "3") (pinfunction "OUT2_3") (pintype "bidirectional"))
      (node (ref "JP3") (pin "2") (pinfunction "2_2") (pintype "passive"))
      (node (ref "SPK1") (pin "1") (pinfunction "1_1") (pintype "bidirectional"))
    )
    (net (code "35") (name "Net-(IC4-PTA0)") (class "Default")
      (node (ref "IC4") (pin "10") (pinfunction "PTA0_10") (pintype "bidirectional"))
      (node (ref "TP1") (pin "TP") (pinfunction "TP_TP") (pintype "input"))
    )
    (net (code "36") (name "Net-(IC4-PTA3)") (class "Default")
      (node (ref "IC4") (pin "13") (pinfunction "PTA3_13") (pintype "bidirectional"))
      (node (ref "TP4") (pin "TP") (pinfunction "TP_TP") (pintype "input"))
    )
    (net (code "37") (name "Net-(IC4-PTA4)") (class "Default")
      (node (ref "IC4") (pin "14") (pinfunction "PTA4_14") (pintype "bidirectional"))
      (node (ref "R33") (pin "1") (pinfunction "1_1") (pintype "passive"))
    )
    (net (code "38") (name "Net-(IC4-PTA18)") (class "Default")
      (node (ref "C21") (pin "1") (pinfunction "1_1") (pintype "passive"))
      (node (ref "IC4") (pin "17") (pinfunction "PTA18_17") (pintype "bidirectional"))
      (node (ref "Q3") (pin "1") (pinfunction "X1_1") (pintype "bidirectional"))
    )
    (net (code "39") (name "Net-(IC4-PTA19)") (class "Default")
      (node (ref "C22") (pin "1") (pinfunction "1_1") (pintype "passive"))
      (node (ref "IC4") (pin "18") (pinfunction "PTA19_18") (pintype "bidirectional"))
      (node (ref "Q3") (pin "3") (pinfunction "X2_3") (pintype "bidirectional"))
    )
    (net (code "40") (name "Net-(IC4-PTA20)") (class "Default")
      (node (ref "C11") (pin "1") (pinfunction "1_1") (pintype "passive"))
      (node (ref "IC4") (pin "19") (pinfunction "PTA20_19") (pintype "bidirectional"))
      (node (ref "R35") (pin "2") (pinfunction "2_2") (pintype "passive"))
      (node (ref "R36") (pin "1") (pinfunction "1_1") (pintype "passive"))
      (node (ref "R44") (pin "1") (pinfunction "1_1") (pintype "passive"))
    )
    (net (code "41") (name "Net-(IC4-PTD4{slash}LLWU_P14)") (class "Default")
      (node (ref "IC4") (pin "29") (pinfunction "PTD4/LLWU_P14_29") (pintype "bidirectional"))
      (node (ref "LED2") (pin "A") (pinfunction "A_A") (pintype "passive"))
    )
    (net (code "42") (name "Net-(IC5A-+IN)") (class "Default")
      (node (ref "C33") (pin "1") (pinfunction "1_1") (pintype "passive"))
      (node (ref "IC5") (pin "3") (pinfunction "+IN_3") (pintype "input"))
      (node (ref "R42") (pin "1") (pinfunction "1_1") (pintype "passive"))
      (node (ref "R43") (pin "2") (pinfunction "2_2") (pintype "passive"))
    )
    (net (code "43") (name "Net-(IC5A--IN)") (class "Default")
      (node (ref "IC5") (pin "4") (pinfunction "-IN_4") (pintype "input"))
      (node (ref "R40") (pin "1") (pinfunction "1_1") (pintype "passive"))
      (node (ref "R41") (pin "2") (pinfunction "2_2") (pintype "passive"))
    )
    (net (code "44") (name "Net-(L1-2)") (class "Default")
      (node (ref "D1") (pin "3") (pinfunction "3_3") (pintype "bidirectional"))
      (node (ref "D1") (pin "4") (pinfunction "4_4") (pintype "bidirectional"))
      (node (ref "L1") (pin "4") (pinfunction "2_4") (pintype "passive"))
      (node (ref "TP14") (pin "TP") (pinfunction "TP_TP") (pintype "input"))
      (node (ref "USB2") (pin "2") (pinfunction "2_2") (pintype "bidirectional"))
    )
    (net (code "45") (name "Net-(L1-3)") (class "Default")
      (node (ref "L1") (pin "2") (pinfunction "3_2") (pintype "passive"))
      (node (ref "R47") (pin "1") (pinfunction "1_1") (pintype "passive"))
    )
    (net (code "46") (name "Net-(L1-4)") (class "Default")
      (node (ref "L1") (pin "3") (pinfunction "4_3") (pintype "passive"))
      (node (ref "R46") (pin "1") (pinfunction "1_1") (pintype "passive"))
    )
    (net (code "47") (name "Net-(L2-Pad1)") (class "Default")
      (node (ref "L2") (pin "1") (pinfunction "1_1") (pintype "passive"))
      (node (ref "USB2") (pin "1") (pinfunction "1_1") (pintype "bidirectional"))
    )
    (net (code "48") (name "Net-(LED2-PadC)") (class "Default")
      (node (ref "LED2") (pin "C") (pinfunction "C_C") (pintype "passive"))
      (node (ref "R34") (pin "1") (pinfunction "1_1") (pintype "passive"))
    )
    (net (code "49") (name "Net-(MIC1-OUT)") (class "Default")
      (node (ref "C32") (pin "2") (pinfunction "2_2") (pintype "passive"))
      (node (ref "MIC1") (pin "4") (pinfunction "OUT_4") (pintype "bidirectional"))
    )
    (net (code "50") (name "Net-(Q1-G)") (class "Default")
      (node (ref "Q1") (pin "1") (pinfunction "G_1") (pintype "passive"))
      (node (ref "R5") (pin "2") (pinfunction "2_2") (pintype "passive"))
    )
    (net (code "51") (name "Net-(Q4-G)") (class "Default")
      (node (ref "Q4") (pin "1") (pinfunction "G_1") (pintype "passive"))
      (node (ref "R21") (pin "2") (pinfunction "2_2") (pintype "passive"))
    )
    (net (code "52") (name "Net-(R4-Pad2)") (class "Default")
      (node (ref "R4") (pin "2") (pinfunction "2_2") (pintype "passive"))
      (node (ref "SPK1") (pin "2") (pinfunction "2_2") (pintype "bidirectional"))
    )
    (net (code "53") (name "Net-(U1-INT1)") (class "Default")
      (node (ref "R29") (pin "2") (pinfunction "2_2") (pintype "passive"))
      (node (ref "U1") (pin "19") (pinfunction "INT1_19") (pintype "bidirectional"))
    )
    (net (code "54") (name "Net-(U1-INT3)") (class "Default")
      (node (ref "R32") (pin "2") (pinfunction "2_2") (pintype "passive"))
      (node (ref "U1") (pin "14") (pinfunction "INT3_14") (pintype "bidirectional"))
    )
    (net (code "55") (name "Net-(U1-INT5)") (class "Default")
      (node (ref "R31") (pin "1") (pinfunction "1_1") (pintype "passive"))
      (node (ref "U1") (pin "10") (pinfunction "INT5_10") (pintype "bidirectional"))
    )
    (net (code "56") (name "P0") (class "Default")
      (node (ref "EXP1") (pin "24") (pinfunction "S_24") (pintype "passive"))
      (node (ref "IC1") (pin "4") (pinfunction "P0.00_4") (pintype "bidirectional"))
      (node (ref "P_4") (pin "1") (pinfunction "1_1") (pintype "bidirectional"))
      (node (ref "R6") (pin "1") (pinfunction "1_1") (pintype "passive"))
    )
    (net (code "57") (name "P1") (class "Default")
      (node (ref "EXP1") (pin "23") (pinfunction "S_23") (pintype "passive"))
      (node (ref "IC1") (pin "5") (pinfunction "P0.01_5") (pintype "bidirectional"))
      (node (ref "P_3") (pin "1") (pinfunction "1_1") (pintype "bidirectional"))
      (node (ref "R7") (pin "1") (pinfunction "1_1") (pintype "passive"))
    )
    (net (code "58") (name "P2") (class "Default")
      (node (ref "EXP1") (pin "22") (pinfunction "S_22") (pintype "passive"))
      (node (ref "IC1") (pin "6") (pinfunction "P0.02_6") (pintype "bidirectional"))
      (node (ref "P_2") (pin "1") (pinfunction "1_1") (pintype "bidirectional"))
      (node (ref "R19") (pin "1") (pinfunction "1_1") (pintype "passive"))
    )
    (net (code "59") (name "P3") (class "Default")
      (node (ref "C34") (pin "1") (pinfunction "1_1") (pintype "passive"))
      (node (ref "IC1") (pin "7") (pinfunction "P0.03_7") (pintype "bidirectional"))
      (node (ref "IC5") (pin "1") (pinfunction "OUT_1") (pintype "output"))
      (node (ref "R41") (pin "1") (pinfunction "1_1") (pintype "passive"))
    )
    (net (code "60") (name "P4") (class "Default")
      (node (ref "EXP1") (pin "20") (pinfunction "S_20") (pintype "passive"))
      (node (ref "IC1") (pin "8") (pinfunction "P0.04_8") (pintype "bidirectional"))
      (node (ref "R1") (pin "1") (pinfunction "1_1") (pintype "passive"))
    )
    (net (code "61") (name "P5") (class "Default")
      (node (ref "EXP1") (pin "19") (pinfunction "S_19") (pintype "passive"))
      (node (ref "IC1") (pin "9") (pinfunction "P0.05_9") (pintype "bidirectional"))
      (node (ref "R8") (pin "1") (pinfunction "1_1") (pintype "passive"))
    )
    (net (code "62") (name "P6") (class "Default")
      (node (ref "EXP1") (pin "18") (pinfunction "S_18") (pintype "passive"))
      (node (ref "IC1") (pin "10") (pinfunction "P0.06_10") (pintype "bidirectional"))
      (node (ref "R9") (pin "1") (pinfunction "1_1") (pintype "passive"))
    )
    (net (code "63") (name "P7") (class "Default")
      (node (ref "EXP1") (pin "17") (pinfunction "S_17") (pintype "passive"))
      (node (ref "IC1") (pin "11") (pinfunction "P0.07_11") (pintype "bidirectional"))
      (node (ref "R10") (pin "1") (pinfunction "1_1") (pintype "passive"))
    )
    (net (code "64") (name "P8") (class "Default")
      (node (ref "EXP1") (pin "16") (pinfunction "S_16") (pintype "passive"))
      (node (ref "IC1") (pin "14") (pinfunction "P0.08_14") (pintype "bidirectional"))
      (node (ref "R11") (pin "1") (pinfunction "1_1") (pintype "passive"))
    )
    (net (code "65") (name "P9") (class "Default")
      (node (ref "EXP1") (pin "15") (pinfunction "S_15") (pintype "passive"))
      (node (ref "IC1") (pin "15") (pinfunction "P0.09_15") (pintype "bidirectional"))
      (node (ref "R12") (pin "1") (pinfunction "1_1") (pintype "passive"))
    )
    (net (code "66") (name "P10") (class "Default")
      (node (ref "EXP1") (pin "12") (pinfunction "S_12") (pintype "passive"))
      (node (ref "IC1") (pin "16") (pinfunction "P0.10_16") (pintype "bidirectional"))
      (node (ref "R13") (pin "1") (pinfunction "1_1") (pintype "passive"))
    )
    (net (code "67") (name "P11") (class "Default")
      (node (ref "EXP1") (pin "11") (pinfunction "S_11") (pintype "passive"))
      (node (ref "IC1") (pin "17") (pinfunction "P0.11_17") (pintype "bidirectional"))
      (node (ref "R14") (pin "1") (pinfunction "1_1") (pintype "passive"))
    )
    (net (code "68") (name "P12") (class "Default")
      (node (ref "EXP1") (pin "10") (pinfunction "S_10") (pintype "passive"))
      (node (ref "IC1") (pin "18") (pinfunction "P0.12_18") (pintype "bidirectional"))
      (node (ref "R15") (pin "1") (pinfunction "1_1") (pintype "passive"))
    )
    (net (code "69") (name "P13") (class "Default")
      (node (ref "EXP1") (pin "9") (pinfunction "S_9") (pintype "passive"))
      (node (ref "IC1") (pin "19") (pinfunction "P0.13_19") (pintype "bidirectional"))
      (node (ref "R16") (pin "1") (pinfunction "1_1") (pintype "passive"))
    )
    (net (code "70") (name "P14") (class "Default")
      (node (ref "EXP1") (pin "8") (pinfunction "S_8") (pintype "passive"))
      (node (ref "IC1") (pin "20") (pinfunction "P0.14_20") (pintype "bidirectional"))
      (node (ref "R17") (pin "1") (pinfunction "1_1") (pintype "passive"))
    )
    (net (code "71") (name "P15") (class "Default")
      (node (ref "EXP1") (pin "7") (pinfunction "S_7") (pintype "passive"))
      (node (ref "IC1") (pin "21") (pinfunction "P0.15_21") (pintype "bidirectional"))
      (node (ref "R18") (pin "1") (pinfunction "1_1") (pintype "passive"))
    )
    (net (code "72") (name "P16") (class "Default")
      (node (ref "IC1") (pin "22") (pinfunction "P0.16_22") (pintype "bidirectional"))
      (node (ref "R2") (pin "1") (pinfunction "1_1") (pintype "passive"))
      (node (ref "TAST_B") (pin "3") (pinfunction "S1_3") (pintype "passive"))
      (node (ref "TAST_B") (pin "4") (pinfunction "S2_4") (pintype "passive"))
    )
    (net (code "73") (name "P17") (class "Default")
      (node (ref "IC1") (pin "25") (pinfunction "P0.17_25") (pintype "bidirectional"))
      (node (ref "R3") (pin "1") (pinfunction "1_1") (pintype "passive"))
      (node (ref "TAST_A") (pin "3") (pinfunction "S1_3") (pintype "passive"))
      (node (ref "TAST_A") (pin "4") (pinfunction "S2_4") (pintype "passive"))
    )
    (net (code "74") (name "P18") (class "Default")
      (node (ref "IC1") (pin "26") (pinfunction "P0.18_26") (pintype "bidirectional"))
      (node (ref "LED1") (pin "1") (pinfunction "DI_1") (pintype "input"))
    )
    (net (code "75") (name "P19") (class "Default")
      (node (ref "IC1") (pin "27") (pinfunction "P0.19_27") (pintype "bidirectional"))
      (node (ref "R24") (pin "1") (pinfunction "1_1") (pintype "passive"))
    )
    (net (code "76") (name "P20") (class "Default")
      (node (ref "IC1") (pin "28") (pinfunction "P0.20_28") (pintype "bidirectional"))
      (node (ref "R23") (pin "1") (pinfunction "1_1") (pintype "passive"))
    )
    (net (code "77") (name "P21") (class "Default")
      (node (ref "IC1") (pin "40") (pinfunction "P0.21_40") (pintype "bidirectional"))
      (node (ref "R29") (pin "1") (pinfunction "1_1") (pintype "passive"))
      (node (ref "R30") (pin "1") (pinfunction "1_1") (pintype "passive"))
      (node (ref "R31") (pin "2") (pinfunction "2_2") (pintype "passive"))
      (node (ref "R32") (pin "1") (pinfunction "1_1") (pintype "passive"))
    )
    (net (code "78") (name "P22") (class "Default")
      (node (ref "EXP1") (pin "21") (pinfunction "S_21") (pintype "passive"))
      (node (ref "IC1") (pin "41") (pinfunction "P0.22_41") (pintype "bidirectional"))
      (node (ref "P_1") (pin "1") (pinfunction "1_1") (pintype "bidirectional"))
      (node (ref "R20") (pin "1") (pinfunction "1_1") (pintype "passive"))
    )
    (net (code "79") (name "P23") (class "Default")
      (node (ref "IC1") (pin "42") (pinfunction "P0.23_42") (pintype "bidirectional"))
    )
    (net (code "80") (name "P24") (class "Default")
      (node (ref "IC1") (pin "43") (pinfunction "P0.24_43") (pintype "bidirectional"))
      (node (ref "R39") (pin "2") (pinfunction "2_2") (pintype "passive"))
    )
    (net (code "81") (name "P25") (class "Default")
      (node (ref "IC1") (pin "44") (pinfunction "P0.25_44") (pintype "bidirectional"))
      (node (ref "R38") (pin "2") (pinfunction "2_2") (pintype "passive"))
    )
    (net (code "82") (name "P26") (class "Default")
      (node (ref "C42") (pin "1") (pinfunction "1_1") (pintype "passive"))
      (node (ref "EXP1") (pin "6") (pinfunction "S_6") (pintype "passive"))
      (node (ref "IC1") (pin "45") (pinfunction "P0.26_45") (pintype "bidirectional"))
      (node (ref "R27") (pin "1") (pinfunction "1_1") (pintype "passive"))
    )
    (net (code "83") (name "P27") (class "Default")
      (node (ref "C41") (pin "1") (pinfunction "1_1") (pintype "passive"))
      (node (ref "EXP1") (pin "5") (pinfunction "S_5") (pintype "passive"))
      (node (ref "IC1") (pin "46") (pinfunction "P0.27_46") (pintype "bidirectional"))
      (node (ref "R28") (pin "1") (pinfunction "1_1") (pintype "passive"))
    )
    (net (code "84") (name "P28") (class "Default")
      (node (ref "IC1") (pin "47") (pinfunction "P0.28_47") (pintype "bidirectional"))
      (node (ref "IC3") (pin "7") (pinfunction "SLEEP_7") (pintype "bidirectional"))
    )
    (net (code "85") (name "P29") (class "Default")
      (node (ref "IC1") (pin "48") (pinfunction "P0.29_48") (pintype "bidirectional"))
      (node (ref "IC3") (pin "6") (pinfunction "IN1_6") (pintype "bidirectional"))
    )
    (net (code "86") (name "P30") (class "Default")
      (node (ref "IC1") (pin "3") (pinfunction "P0.30_3") (pintype "bidirectional"))
      (node (ref "IC3") (pin "5") (pinfunction "IN2_5") (pintype "bidirectional"))
    )
    (net (code "87") (name "RESET_SW") (class "Default")
      (node (ref "C20") (pin "1") (pinfunction "1_1") (pintype "passive"))
      (node (ref "IC4") (pin "21") (pinfunction "PTB1_21") (pintype "bidirectional"))
      (node (ref "R22") (pin "1") (pinfunction "1_1") (pintype "passive"))
      (node (ref "TAST_RESET") (pin "3") (pinfunction "S_3") (pintype "passive"))
      (node (ref "TAST_RESET") (pin "4") (pinfunction "S1_4") (pintype "passive"))
    )
    (net (code "88") (name "RX") (class "Default")
      (node (ref "R27") (pin "2") (pinfunction "2_2") (pintype "passive"))
      (node (ref "SERIAL") (pin "1") (pinfunction "1_1") (pintype "bidirectional"))
    )
    (net (code "89") (name "SCK") (class "Default")
      (node (ref "IC4") (pin "30") (pinfunction "PTD5_30") (pintype "bidirectional"))
      (node (ref "IC6") (pin "2") (pinfunction "C_2") (pintype "bidirectional"))
    )
    (net (code "90") (name "SCL{slash}P19") (class "Default")
      (node (ref "EXP1") (pin "3") (pinfunction "S_3") (pintype "passive"))
      (node (ref "I2C") (pin "1") (pinfunction "1_1") (pintype "bidirectional"))
      (node (ref "R24") (pin "2") (pinfunction "2_2") (pintype "passive"))
      (node (ref "R26") (pin "1") (pinfunction "1_1") (pintype "passive"))
      (node (ref "U1") (pin "9") (pinfunction "SCX_9") (pintype "bidirectional"))
    )
    (net (code "91") (name "SDA{slash}P20") (class "Default")
      (node (ref "EXP1") (pin "4") (pinfunction "S_4") (pintype "passive"))
      (node (ref "I2C") (pin "2") (pinfunction "2_2") (pintype "bidirectional"))
      (node (ref "R23") (pin "2") (pinfunction "2_2") (pintype "passive"))
      (node (ref "R25") (pin "1") (pinfunction "1_1") (pintype "passive"))
      (node (ref "U1") (pin "11") (pinfunction "SDX_11") (pintype "bidirectional"))
    )
    (net (code "92") (name "SWDCLK") (class "Default")
      (node (ref "IC1") (pin "24") (pinfunction "SWDCLK_24") (pintype "bidirectional"))
      (node (ref "IC4") (pin "26") (pinfunction "PTC5/LLWU_P9_26") (pintype "bidirectional"))
      (node (ref "TP7") (pin "TP") (pinfunction "TP_TP") (pintype "input"))
    )
    (net (code "93") (name "SWDIO{slash}RESET") (class "Default")
      (node (ref "IC1") (pin "23") (pinfunction "SWDIO/NRESET_23") (pintype "bidirectional"))
      (node (ref "IC4") (pin "27") (pinfunction "PTC6/LLWU_P10_27") (pintype "bidirectional"))
      (node (ref "R37") (pin "1") (pinfunction "1_1") (pintype "passive"))
      (node (ref "TP8") (pin "TP") (pinfunction "TP_TP") (pintype "input"))
    )
    (net (code "94") (name "TO_P24") (class "Default")
      (node (ref "IC4") (pin "24") (pinfunction "PTC3/LLWU_P7_24") (pintype "bidirectional"))
      (node (ref "R39") (pin "1") (pinfunction "1_1") (pintype "passive"))
      (node (ref "TP6") (pin "TP") (pinfunction "TP_TP") (pintype "input"))
    )
    (net (code "95") (name "TO_P25") (class "Default")
      (node (ref "IC4") (pin "25") (pinfunction "PTC4/LLWU_P8_25") (pintype "bidirectional"))
      (node (ref "R38") (pin "1") (pinfunction "1_1") (pintype "passive"))
      (node (ref "TP9") (pin "TP") (pinfunction "TP_TP") (pintype "input"))
    )
    (net (code "96") (name "TX") (class "Default")
      (node (ref "R28") (pin "2") (pinfunction "2_2") (pintype "passive"))
      (node (ref "SERIAL") (pin "2") (pinfunction "2_2") (pintype "bidirectional"))
    )
    (net (code "97") (name "USB_DM") (class "Default")
      (node (ref "C40") (pin "1") (pinfunction "1_1") (pintype "passive"))
      (node (ref "IC4") (pin "4") (pinfunction "USB0_DM_4") (pintype "passive"))
      (node (ref "R46") (pin "2") (pinfunction "2_2") (pintype "passive"))
    )
    (net (code "98") (name "USB_DP") (class "Default")
      (node (ref "C39") (pin "1") (pinfunction "1_1") (pintype "passive"))
      (node (ref "IC4") (pin "3") (pinfunction "USB0_DP_3") (pintype "passive"))
      (node (ref "R47") (pin "2") (pinfunction "2_2") (pintype "passive"))
    )
    (net (code "99") (name "USB_VREG") (class "Default")
      (node (ref "C37") (pin "1") (pinfunction "1_1") (pintype "passive"))
      (node (ref "C38") (pin "1") (pinfunction "1_1") (pintype "passive"))
      (node (ref "C4") (pin "1") (pinfunction "1_1") (pintype "passive"))
      (node (ref "C5") (pin "1") (pinfunction "1_1") (pintype "passive"))
      (node (ref "IC4") (pin "15") (pinfunction "VDD_15") (pintype "power_in"))
      (node (ref "IC4") (pin "5") (pinfunction "VOUT33_5") (pintype "output"))
      (node (ref "IC4") (pin "7") (pinfunction "VDDA_7") (pintype "power_in"))
      (node (ref "IC6") (pin "6") (pinfunction "VCC_6") (pintype "bidirectional"))
      (node (ref "Q4") (pin "3") (pinfunction "D_3") (pintype "passive"))
      (node (ref "R22") (pin "2") (pinfunction "2_2") (pintype "passive"))
      (node (ref "R33") (pin "2") (pinfunction "2_2") (pintype "passive"))
      (node (ref "R34") (pin "2") (pinfunction "2_2") (pintype "passive"))
      (node (ref "TP5") (pin "TP") (pinfunction "TP_TP") (pintype "input"))
    )
    (net (code "100") (name "VCC") (class "Default")
      (node (ref "C1") (pin "1") (pinfunction "1_1") (pintype "passive"))
      (node (ref "C10") (pin "1") (pinfunction "1_1") (pintype "passive"))
      (node (ref "C15") (pin "1") (pinfunction "1_1") (pintype "passive"))
      (node (ref "C17") (pin "1") (pinfunction "1_1") (pintype "passive"))
      (node (ref "C18") (pin "1") (pinfunction "1_1") (pintype "passive"))
      (node (ref "C2") (pin "1") (pinfunction "1_1") (pintype "passive"))
      (node (ref "C24") (pin "1") (pinfunction "1_1") (pintype "passive"))
      (node (ref "C29") (pin "1") (pinfunction "1_1") (pintype "passive"))
      (node (ref "C3") (pin "+") (pinfunction "+_+") (pintype "passive"))
      (node (ref "C30") (pin "1") (pinfunction "1_1") (pintype "passive"))
      (node (ref "C31") (pin "1") (pinfunction "1_1") (pintype "passive"))
      (node (ref "C35") (pin "1") (pinfunction "1_1") (pintype "passive"))
      (node (ref "C36") (pin "1") (pinfunction "1_1") (pintype "passive"))
      (node (ref "C7") (pin "1") (pinfunction "1_1") (pintype "passive"))
      (node (ref "C8") (pin "1") (pinfunction "1_1") (pintype "passive"))
      (node (ref "C9") (pin "1") (pinfunction "1_1") (pintype "passive"))
      (node (ref "D3") (pin "A") (pinfunction "A_A") (pintype "passive"))
      (node (ref "EXP1") (pin "2") (pinfunction "S_2") (pintype "passive"))
      (node (ref "EXP1") (pin "25") (pinfunction "S_25") (pintype "passive"))
      (node (ref "F1") (pin "1") (pinfunction "1_1") (pintype "passive"))
      (node (ref "I2C") (pin "3") (pinfunction "3_3") (pintype "bidirectional"))
      (node (ref "IC1") (pin "1") (pinfunction "VDD_1") (pintype "bidirectional"))
      (node (ref "IC1") (pin "12") (pinfunction "VDD_2_12") (pintype "bidirectional"))
      (node (ref "IC1") (pin "29") (pinfunction "DEC2_29") (pintype "bidirectional"))
      (node (ref "IC1") (pin "35") (pinfunction "AVDD_35") (pintype "bidirectional"))
      (node (ref "IC1") (pin "36") (pinfunction "AVDD_2_36") (pintype "bidirectional"))
      (node (ref "IC3") (pin "8") (pinfunction "VCC_8") (pintype "bidirectional"))
      (node (ref "IC5") (pin "5") (pinfunction "V+_5") (pintype "power_in"))
      (node (ref "LED1") (pin "2") (pinfunction "VDD_2") (pintype "power_in"))
      (node (ref "MIC1") (pin "1") (pinfunction "VDD_1") (pintype "bidirectional"))
      (node (ref "Q1") (pin "2") (pinfunction "S_2") (pintype "passive"))
      (node (ref "Q4") (pin "2") (pinfunction "S_2") (pintype "passive"))
      (node (ref "R19") (pin "2") (pinfunction "2_2") (pintype "passive"))
      (node (ref "R2") (pin "2") (pinfunction "2_2") (pintype "passive"))
      (node (ref "R20") (pin "2") (pinfunction "2_2") (pintype "passive"))
      (node (ref "R25") (pin "2") (pinfunction "2_2") (pintype "passive"))
      (node (ref "R26") (pin "2") (pinfunction "2_2") (pintype "passive"))
      (node (ref "R3") (pin "2") (pinfunction "2_2") (pintype "passive"))
      (node (ref "R30") (pin "2") (pinfunction "2_2") (pintype "passive"))
      (node (ref "R37") (pin "2") (pinfunction "2_2") (pintype "passive"))
      (node (ref "R42") (pin "2") (pinfunction "2_2") (pintype "passive"))
      (node (ref "R6") (pin "2") (pinfunction "2_2") (pintype "passive"))
      (node (ref "R7") (pin "2") (pinfunction "2_2") (pintype "passive"))
      (node (ref "SERIAL") (pin "3") (pinfunction "3_3") (pintype "bidirectional"))
      (node (ref "U1") (pin "13") (pinfunction "VDDIO_13") (pintype "bidirectional"))
      (node (ref "U1") (pin "3") (pinfunction "VDD_3") (pintype "bidirectional"))
      (node (ref "U1") (pin "7") (pinfunction "PS_7") (pintype "bidirectional"))
    )
    (net (code "101") (name "VM") (class "Default")
      (node (ref "C16") (pin "1") (pinfunction "1_1") (pintype "passive"))
      (node (ref "C26") (pin "1") (pinfunction "1_1") (pintype "passive"))
      (node (ref "D3") (pin "C") (pinfunction "C_C") (pintype "passive"))
      (node (ref "IC3") (pin "1") (pinfunction "VM_1") (pintype "bidirectional"))
      (node (ref "JP3") (pin "5") (pinfunction "5_5") (pintype "passive"))
    )
    (net (code "102") (name "unconnected-(IC1-DCC-Pad2)") (class "Default")
      (node (ref "IC1") (pin "2") (pinfunction "DCC_2") (pintype "bidirectional"))
    )
    (net (code "103") (name "unconnected-(IC4-PTA1-Pad11)") (class "Default")
      (node (ref "IC4") (pin "11") (pinfunction "PTA1_11") (pintype "bidirectional"))
    )
    (net (code "104") (name "unconnected-(IC4-PTA2-Pad12)") (class "Default")
      (node (ref "IC4") (pin "12") (pinfunction "PTA2_12") (pintype "bidirectional"))
    )
    (net (code "105") (name "unconnected-(IC4-PTE0-Pad1)") (class "Default")
      (node (ref "IC4") (pin "1") (pinfunction "PTE0_1") (pintype "bidirectional"))
    )
    (net (code "106") (name "unconnected-(IC4-PTE30-Pad9)") (class "Default")
      (node (ref "IC4") (pin "9") (pinfunction "PTE30_9") (pintype "bidirectional"))
    )
    (net (code "107") (name "unconnected-(LED1-DO-Pad3)") (class "Default")
      (node (ref "LED1") (pin "3") (pinfunction "DO_3") (pintype "output"))
    )
    (net (code "108") (name "unconnected-(U1-CSB1-Pad16)") (class "Default")
      (node (ref "U1") (pin "16") (pinfunction "CSB1_16") (pintype "bidirectional"))
    )
    (net (code "109") (name "unconnected-(U1-CSB2-Pad5)") (class "Default")
      (node (ref "U1") (pin "5") (pinfunction "CSB2_5") (pintype "bidirectional"))
    )
    (net (code "110") (name "unconnected-(U1-DRDYM-Pad2)") (class "Default")
      (node (ref "U1") (pin "2") (pinfunction "DRDYM_2") (pintype "bidirectional"))
    )
    (net (code "111") (name "unconnected-(U1-INT2-Pad1)") (class "Default")
      (node (ref "U1") (pin "1") (pinfunction "INT2_1") (pintype "bidirectional"))
    )
    (net (code "112") (name "unconnected-(U1-INT4-Pad15)") (class "Default")
      (node (ref "U1") (pin "15") (pinfunction "INT4_15") (pintype "bidirectional"))
    )
    (net (code "113") (name "unconnected-(U1-N{slash}C-Pad8)") (class "Default")
      (node (ref "U1") (pin "8") (pinfunction "N/C_8") (pintype "bidirectional"))
    )
    (net (code "114") (name "unconnected-(U1-N{slash}C-Pad18)") (class "Default")
      (node (ref "U1") (pin "18") (pinfunction "N/C_18") (pintype "bidirectional"))
    )
    (net (code "115") (name "unconnected-(USB2-Pad4)") (class "Default")
      (node (ref "USB2") (pin "4") (pinfunction "4_4") (pintype "bidirectional"))
    )
  )
)
